# frontend7.net
KiCad netlist of a schematic drawn in EAGLE
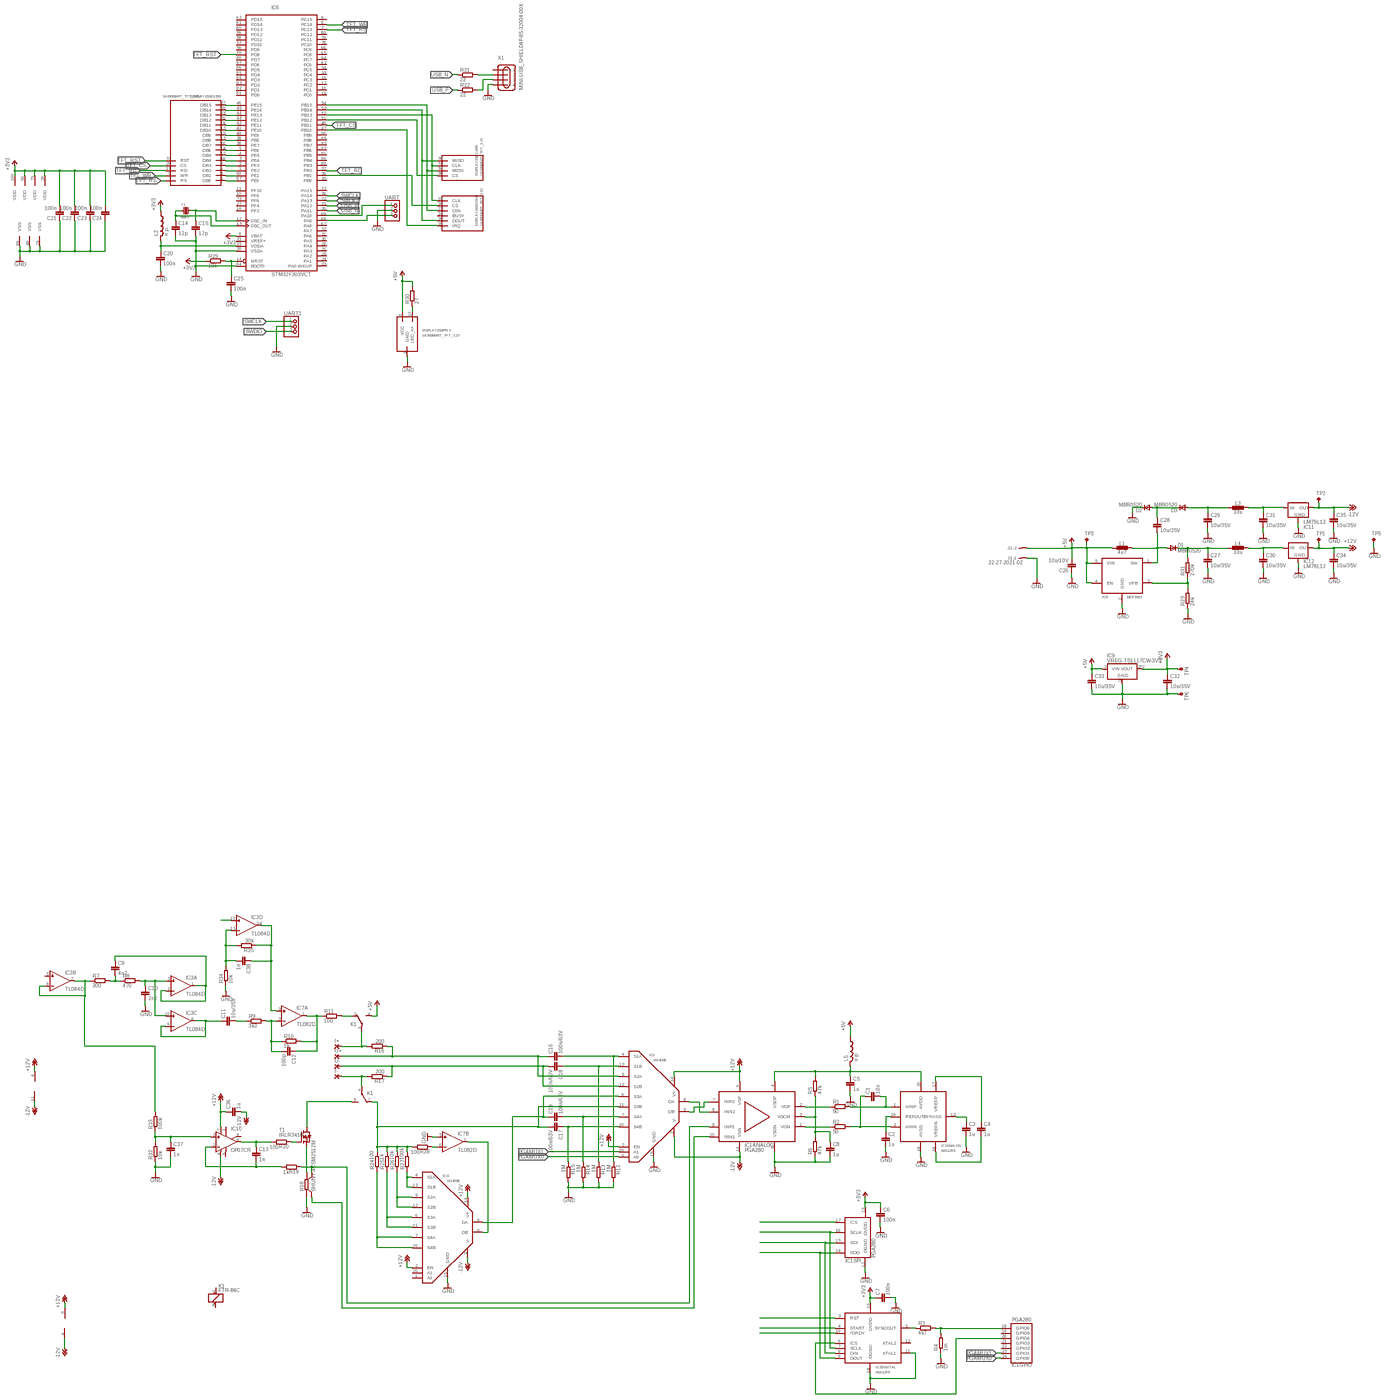
[diagram p0: schematic, sheet 1, overview]
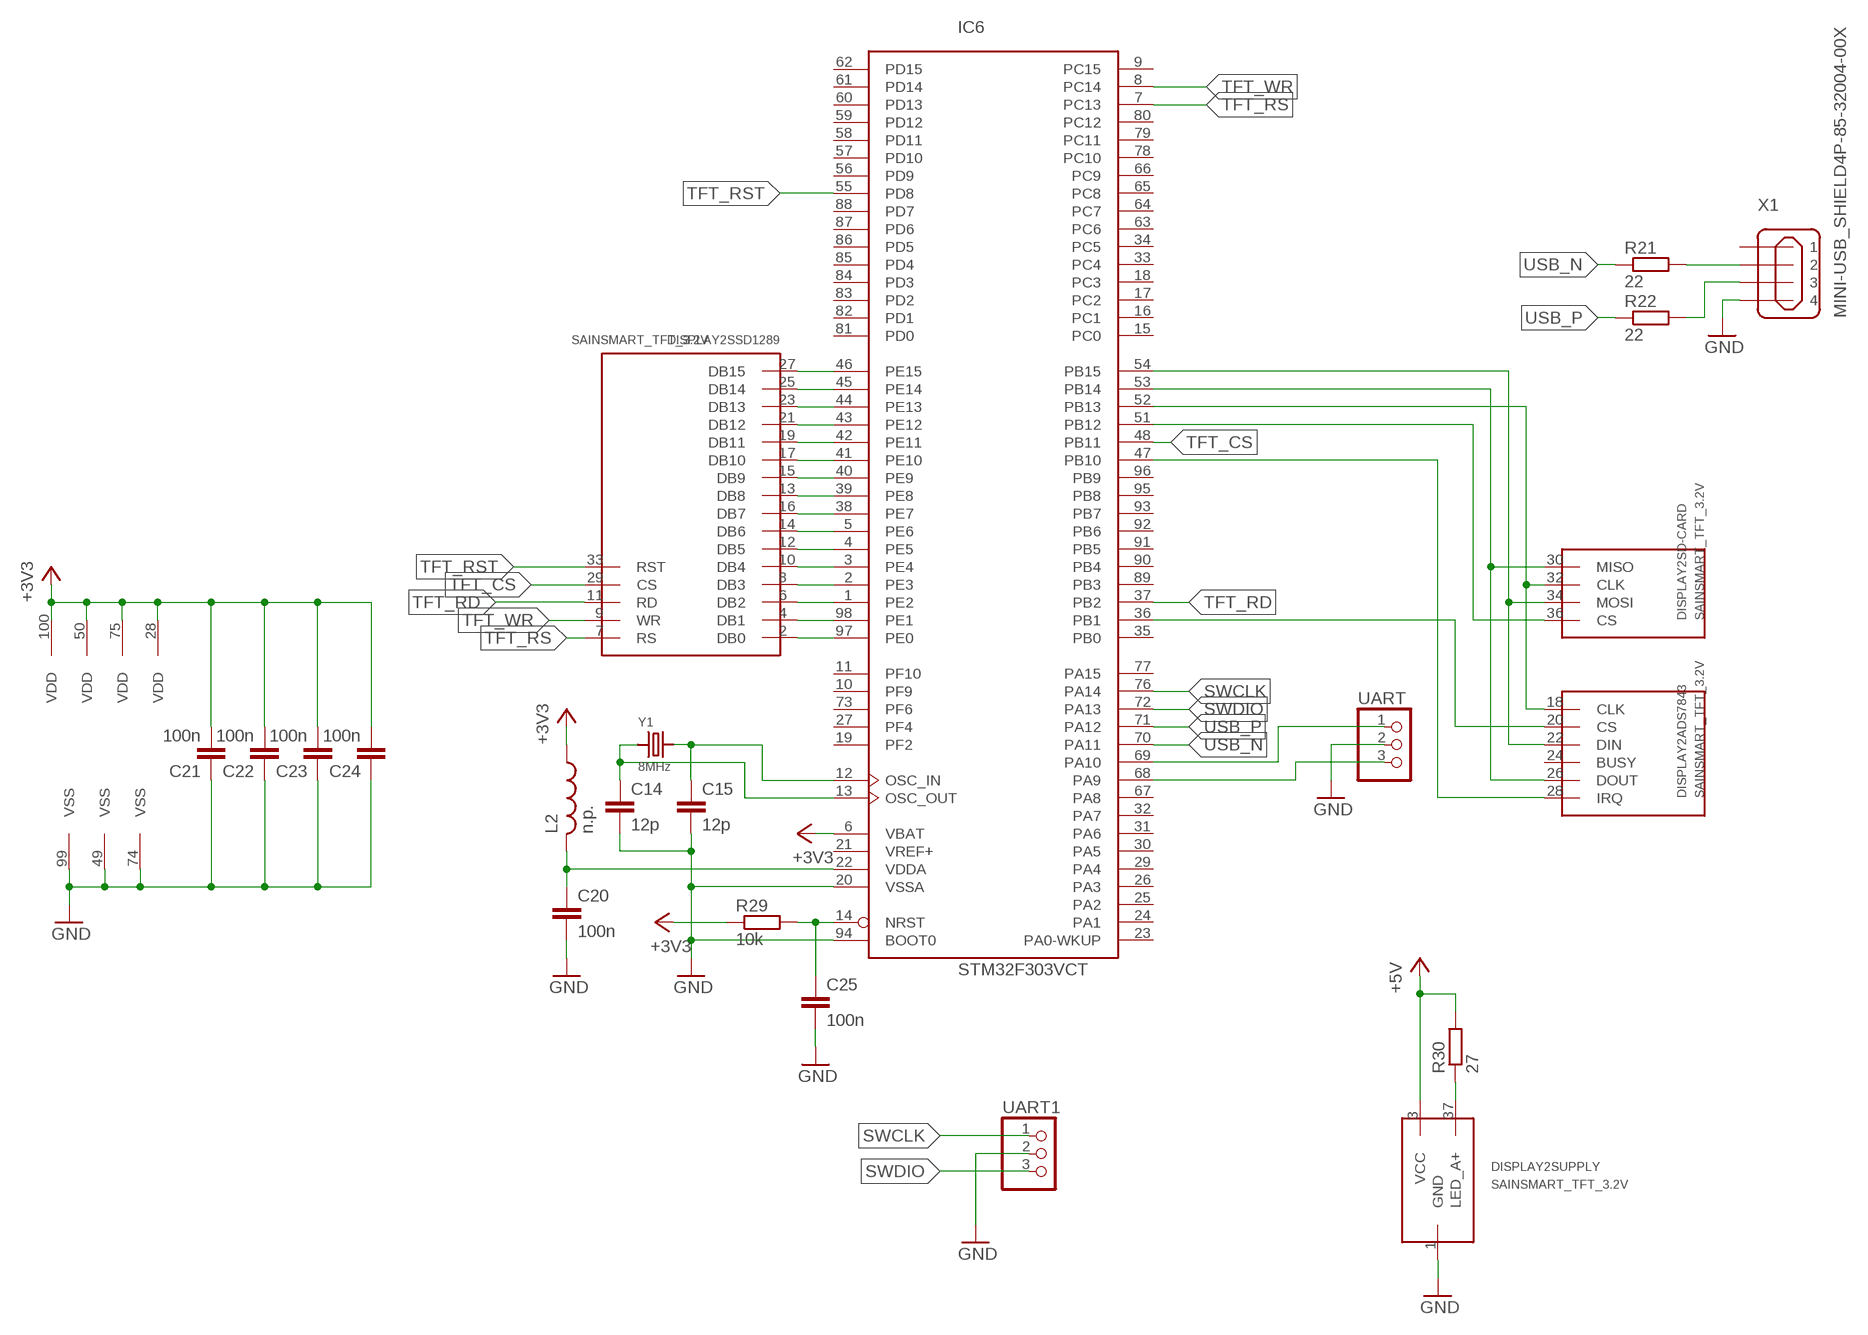
[diagram p1: schematic, sheet 1, part 1 of 4]
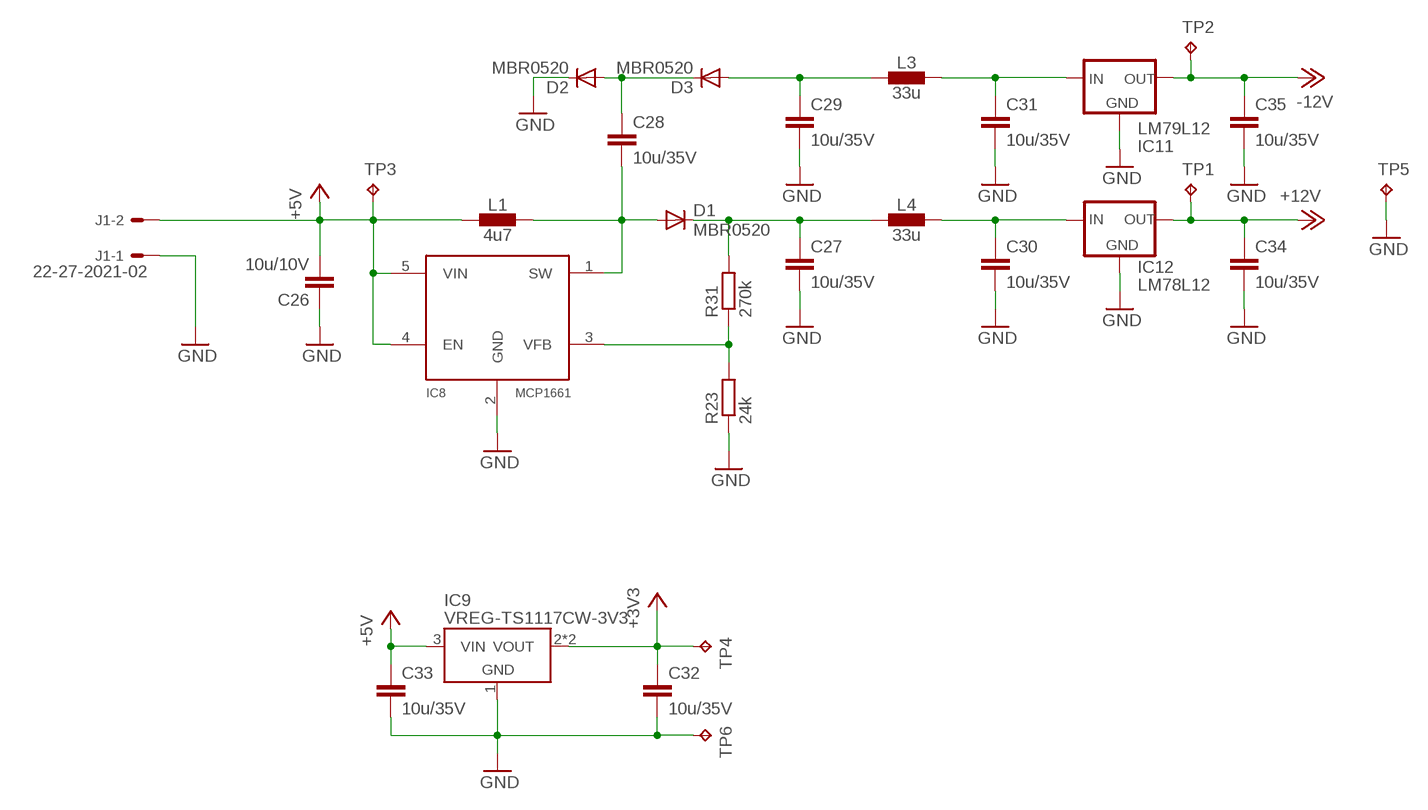
[diagram p2: schematic, sheet 1, part 2 of 4]
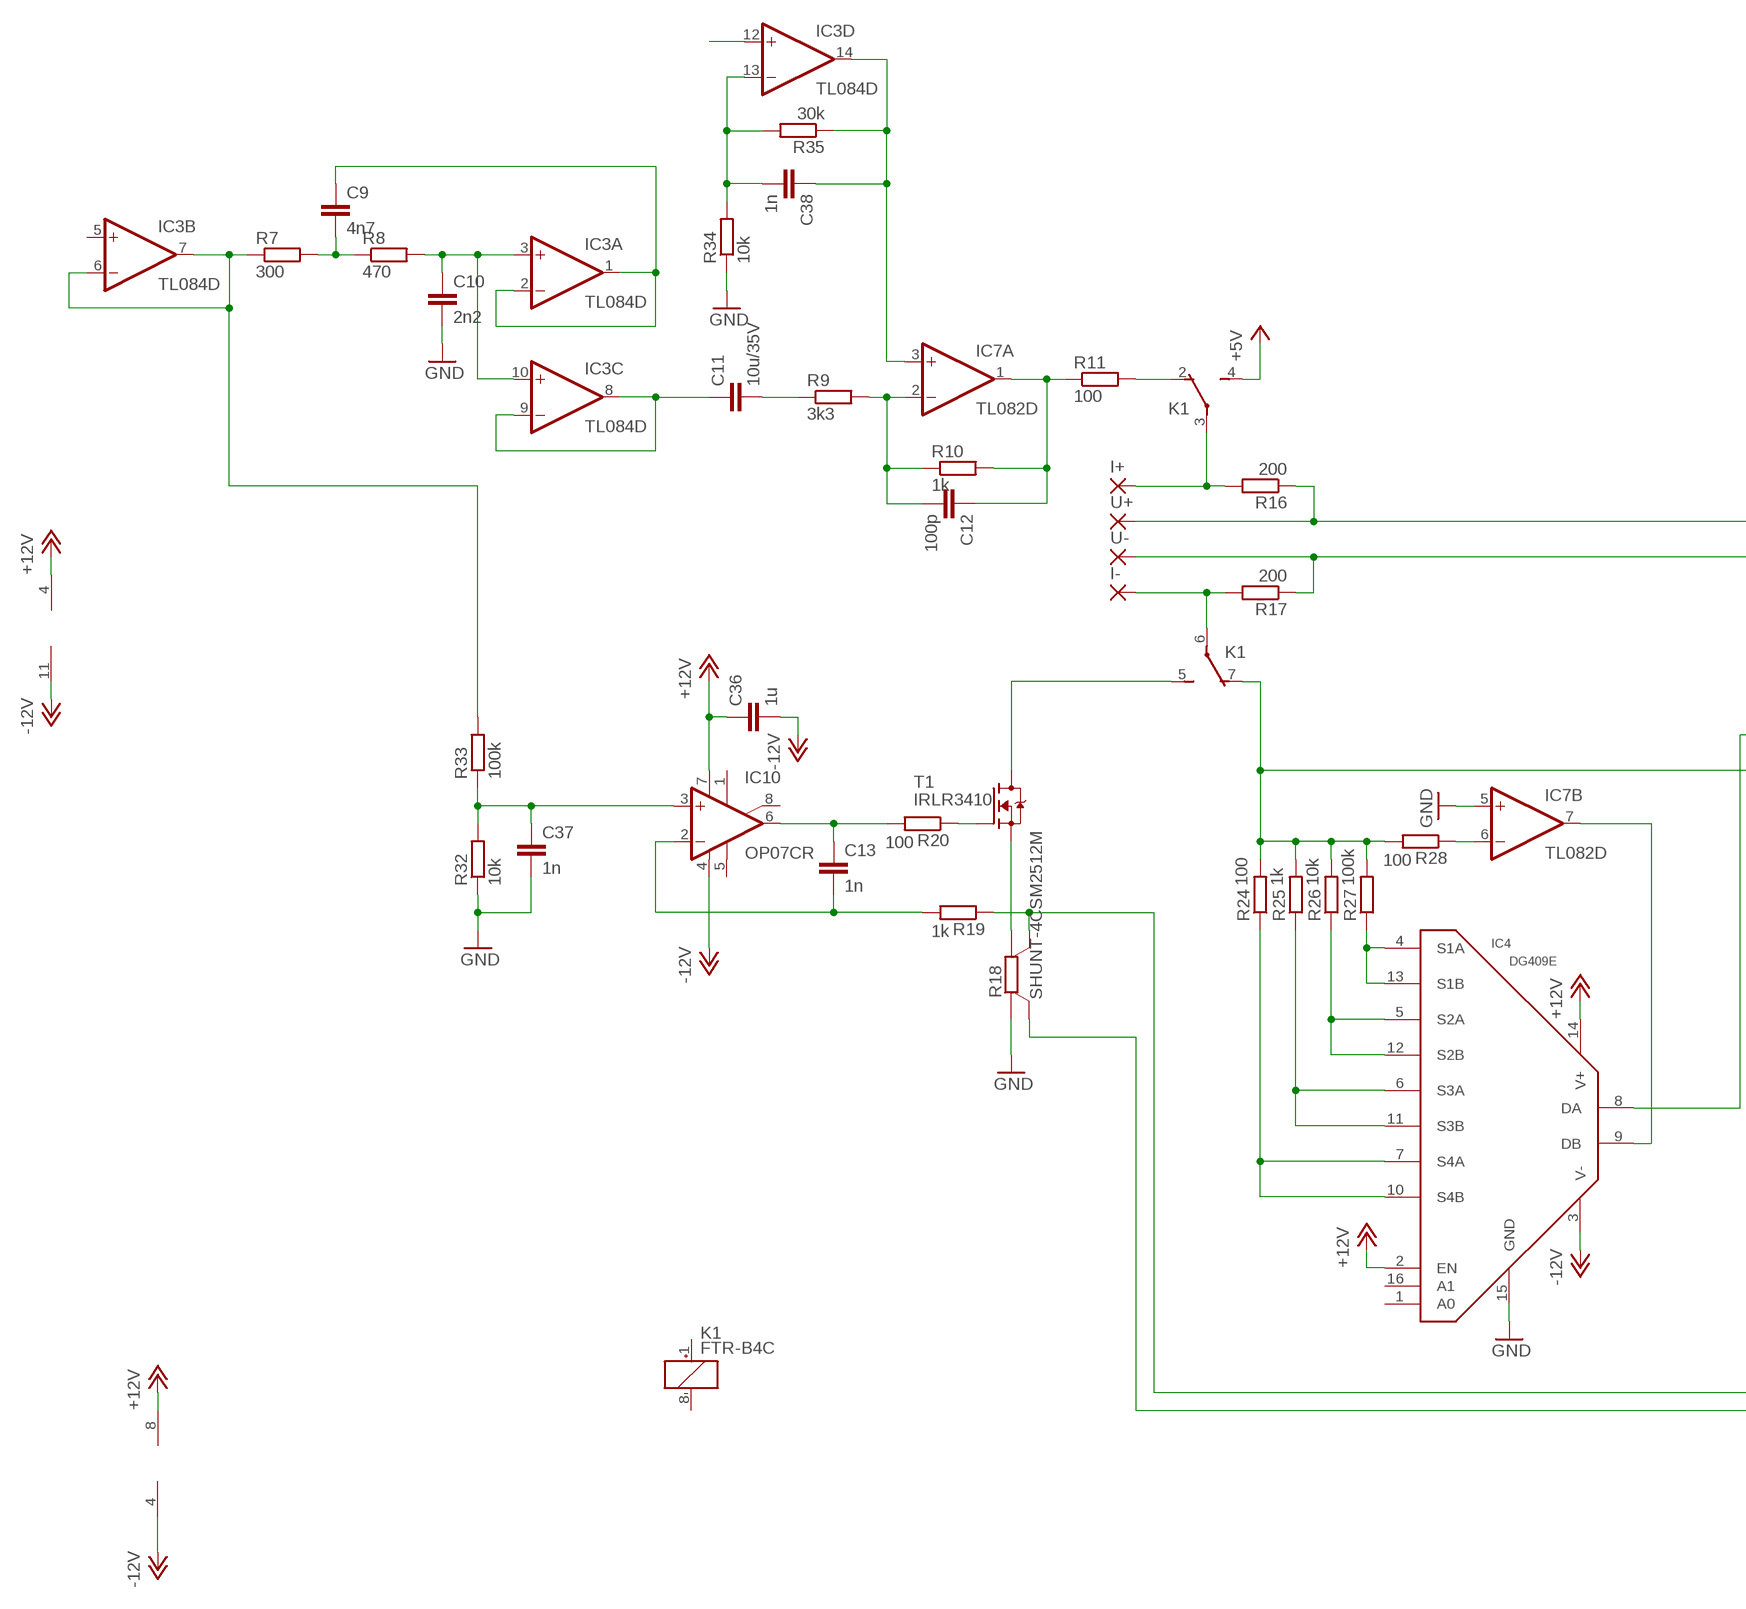
[diagram p3: schematic, sheet 1, part 3 of 4]
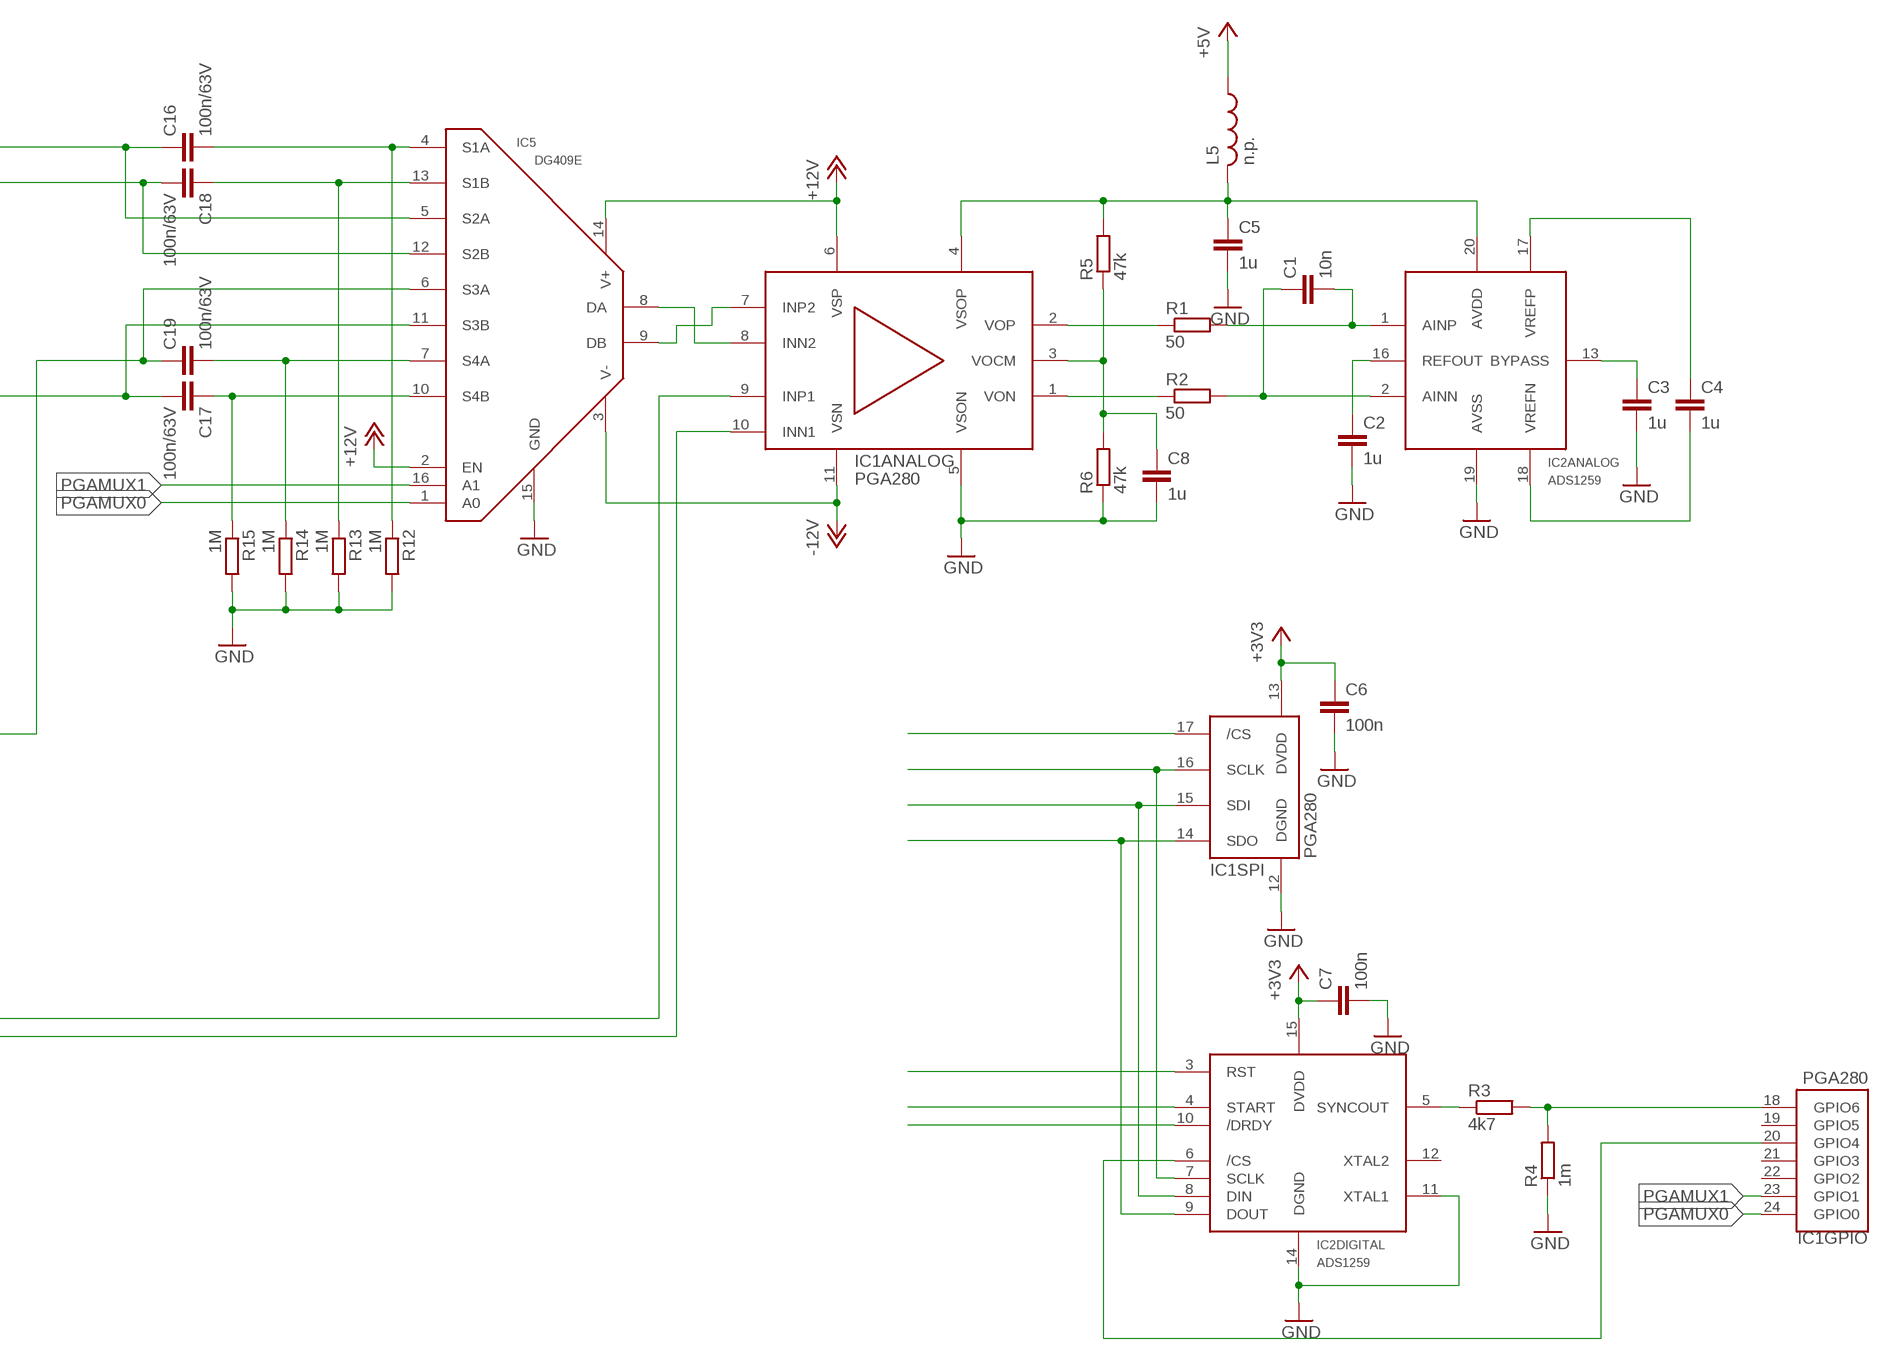
[diagram p4: schematic, sheet 1, part 4 of 4]

(export (version "E")
  (design (tool "Eeschema 10.0.6"))
  (components
    (comp (ref "C1")
      (value "10n")
      (footprint "eagle-import:C0603K")
      (libsource (lib "eagle-import") (part "C-EUC0603K"))
    )
    (comp (ref "C2")
      (value "1u")
      (footprint "eagle-import:C0603K")
      (libsource (lib "eagle-import") (part "C-EUC0603K"))
    )
    (comp (ref "C3")
      (value "1u")
      (footprint "eagle-import:C0603K")
      (libsource (lib "eagle-import") (part "C-EUC0603K"))
    )
    (comp (ref "C4")
      (value "1u")
      (footprint "eagle-import:C0603K")
      (libsource (lib "eagle-import") (part "C-EUC0603K"))
    )
    (comp (ref "C5")
      (value "1u")
      (footprint "eagle-import:C0603K")
      (libsource (lib "eagle-import") (part "C-EUC0603K"))
    )
    (comp (ref "C6")
      (value "100n")
      (footprint "eagle-import:C0603K")
      (libsource (lib "eagle-import") (part "C-EUC0603K"))
    )
    (comp (ref "C7")
      (value "100n")
      (footprint "eagle-import:C0603K")
      (libsource (lib "eagle-import") (part "C-EUC0603K"))
    )
    (comp (ref "C8")
      (value "1u")
      (footprint "eagle-import:C0603K")
      (libsource (lib "eagle-import") (part "C-EUC0603K"))
    )
    (comp (ref "C9")
      (value "4n7")
      (footprint "eagle-import:C0603K")
      (libsource (lib "eagle-import") (part "C-EUC0603K"))
    )
    (comp (ref "C10")
      (value "2n2")
      (footprint "eagle-import:C0603K")
      (libsource (lib "eagle-import") (part "C-EUC0603K"))
    )
    (comp (ref "C11")
      (value "10u/35V")
      (footprint "eagle-import:C1206K")
      (libsource (lib "eagle-import") (part "C-EUC1206K"))
    )
    (comp (ref "C12")
      (value "100p")
      (footprint "eagle-import:C0603K")
      (libsource (lib "eagle-import") (part "C-EUC0603K"))
    )
    (comp (ref "C13")
      (value "1n")
      (footprint "eagle-import:C0603K")
      (libsource (lib "eagle-import") (part "C-EUC0603K"))
    )
    (comp (ref "C14")
      (value "12p")
      (footprint "eagle-import:C0603K")
      (libsource (lib "eagle-import") (part "C-EUC0603K"))
    )
    (comp (ref "C15")
      (value "12p")
      (footprint "eagle-import:C0603K")
      (libsource (lib "eagle-import") (part "C-EUC0603K"))
    )
    (comp (ref "C16")
      (value "100n/63V")
      (footprint "eagle-import:C1206K")
      (libsource (lib "eagle-import") (part "C-EUC1206K"))
    )
    (comp (ref "C17")
      (value "100n/63V")
      (footprint "eagle-import:C1206K")
      (libsource (lib "eagle-import") (part "C-EUC1206K"))
    )
    (comp (ref "C18")
      (value "100n/63V")
      (footprint "eagle-import:C1206K")
      (libsource (lib "eagle-import") (part "C-EUC1206K"))
    )
    (comp (ref "C19")
      (value "100n/63V")
      (footprint "eagle-import:C1206K")
      (libsource (lib "eagle-import") (part "C-EUC1206K"))
    )
    (comp (ref "C20")
      (value "100n")
      (footprint "eagle-import:C0603K")
      (libsource (lib "eagle-import") (part "C-EUC0603K"))
    )
    (comp (ref "C21")
      (value "100n")
      (footprint "eagle-import:C0603K")
      (libsource (lib "eagle-import") (part "C-EUC0603K"))
    )
    (comp (ref "C22")
      (value "100n")
      (footprint "eagle-import:C0603K")
      (libsource (lib "eagle-import") (part "C-EUC0603K"))
    )
    (comp (ref "C23")
      (value "100n")
      (footprint "eagle-import:C0603K")
      (libsource (lib "eagle-import") (part "C-EUC0603K"))
    )
    (comp (ref "C24")
      (value "100n")
      (footprint "eagle-import:C0603K")
      (libsource (lib "eagle-import") (part "C-EUC0603K"))
    )
    (comp (ref "C25")
      (value "100n")
      (footprint "eagle-import:C0603K")
      (libsource (lib "eagle-import") (part "C-EUC0603K"))
    )
    (comp (ref "C26")
      (value "10u/10V")
      (footprint "eagle-import:C1206K")
      (libsource (lib "eagle-import") (part "C-EUC1206K"))
    )
    (comp (ref "C27")
      (value "10u/35V")
      (footprint "eagle-import:C1206K")
      (libsource (lib "eagle-import") (part "C-EUC1206K"))
    )
    (comp (ref "C28")
      (value "10u/35V")
      (footprint "eagle-import:C1206K")
      (libsource (lib "eagle-import") (part "C-EUC1206K"))
    )
    (comp (ref "C29")
      (value "10u/35V")
      (footprint "eagle-import:C1206K")
      (libsource (lib "eagle-import") (part "C-EUC1206K"))
    )
    (comp (ref "C30")
      (value "10u/35V")
      (footprint "eagle-import:C1206K")
      (libsource (lib "eagle-import") (part "C-EUC1206K"))
    )
    (comp (ref "C31")
      (value "10u/35V")
      (footprint "eagle-import:C1206K")
      (libsource (lib "eagle-import") (part "C-EUC1206K"))
    )
    (comp (ref "C32")
      (value "10u/35V")
      (footprint "eagle-import:C1206K")
      (libsource (lib "eagle-import") (part "C-EUC1206K"))
    )
    (comp (ref "C33")
      (value "10u/35V")
      (footprint "eagle-import:C1206K")
      (libsource (lib "eagle-import") (part "C-EUC1206K"))
    )
    (comp (ref "C34")
      (value "10u/35V")
      (footprint "eagle-import:C1206K")
      (libsource (lib "eagle-import") (part "C-EUC1206K"))
    )
    (comp (ref "C35")
      (value "10u/35V")
      (footprint "eagle-import:C1206K")
      (libsource (lib "eagle-import") (part "C-EUC1206K"))
    )
    (comp (ref "C36")
      (value "1u")
      (footprint "eagle-import:C0603K")
      (libsource (lib "eagle-import") (part "C-EUC0603K"))
    )
    (comp (ref "C37")
      (value "1n")
      (footprint "eagle-import:C0603K")
      (libsource (lib "eagle-import") (part "C-EUC0603K"))
    )
    (comp (ref "C38")
      (value "1n")
      (footprint "eagle-import:C0603K")
      (libsource (lib "eagle-import") (part "C-EUC0603K"))
    )
    (comp (ref "D1")
      (value "MBR0520")
      (footprint "eagle-import:SOD123")
      (libsource (lib "eagle-import") (part "DIODE-SOD123"))
    )
    (comp (ref "D2")
      (value "MBR0520")
      (footprint "eagle-import:SOD123")
      (libsource (lib "eagle-import") (part "DIODE-SOD123"))
    )
    (comp (ref "D3")
      (value "MBR0520")
      (footprint "eagle-import:SOD123")
      (libsource (lib "eagle-import") (part "DIODE-SOD123"))
    )
    (comp (ref "DISPLAY2")
      (value "SAINSMART_TFT_3.2V")
      (footprint "eagle-import:SAINSMART_ANGLED")
      (libsource (lib "eagle-import") (part "SAINSMART_TFT_3.2V"))
    )
    (comp (ref "I+")
      (value "SMD5")
      (footprint "eagle-import:SMD2,54-5,08")
      (libsource (lib "eagle-import") (part "SMD5"))
    )
    (comp (ref "I-")
      (value "SMD5")
      (footprint "eagle-import:SMD2,54-5,08")
      (libsource (lib "eagle-import") (part "SMD5"))
    )
    (comp (ref "IC1")
      (value "PGA280")
      (footprint "eagle-import:TSSOP24")
      (libsource (lib "eagle-import") (part "PGA280"))
    )
    (comp (ref "IC2")
      (value "ADS1259")
      (footprint "eagle-import:TSSOP20")
      (libsource (lib "eagle-import") (part "ADS1259"))
    )
    (comp (ref "IC3")
      (value "TL084D")
      (footprint "eagle-import:SO14")
      (libsource (lib "eagle-import") (part "TL084D"))
    )
    (comp (ref "IC4")
      (value "DG409E")
      (footprint "eagle-import:TSSOP16")
      (libsource (lib "eagle-import") (part "DG409E"))
    )
    (comp (ref "IC5")
      (value "DG409E")
      (footprint "eagle-import:TSSOP16")
      (libsource (lib "eagle-import") (part "DG409E"))
    )
    (comp (ref "IC6")
      (value "STM32F303VCT")
      (footprint "eagle-import:LQFP100")
      (libsource (lib "eagle-import") (part "STM32F303VTC"))
    )
    (comp (ref "IC7")
      (value "TL082D")
      (footprint "eagle-import:SO08")
      (libsource (lib "eagle-import") (part "TL082D"))
    )
    (comp (ref "IC8")
      (value "MCP1661")
      (footprint "eagle-import:SOT23-5")
      (libsource (lib "eagle-import") (part "MCP1661"))
    )
    (comp (ref "IC9")
      (value "VREG-TS1117CW-3V3")
      (footprint "eagle-import:SOT223")
      (libsource (lib "eagle-import") (part "VREG-TS1117CW-3V3"))
    )
    (comp (ref "IC10")
      (value "OP07CR")
      (footprint "eagle-import:SO08")
      (libsource (lib "eagle-import") (part "OP07RC"))
    )
    (comp (ref "IC11")
      (value "LM79L12")
      (footprint "eagle-import:SO08")
      (libsource (lib "eagle-import") (part "79LXX-SO_INALL"))
    )
    (comp (ref "IC12")
      (value "LM78L12")
      (footprint "eagle-import:SO08")
      (libsource (lib "eagle-import") (part "78LXX-SO8_GNDALL"))
    )
    (comp (ref "J1")
      (value "22-27-2021-02")
      (footprint "eagle-import:6410-02")
      (libsource (lib "eagle-import") (part "22-?-0227-2021"))
    )
    (comp (ref "K1")
      (value "FTR-B4C")
      (footprint "eagle-import:FTR-B4C")
      (libsource (lib "eagle-import") (part "FTR-B4C"))
    )
    (comp (ref "L1")
      (value "4u7")
      (footprint "eagle-import:L_NR60XX")
      (libsource (lib "eagle-import") (part "INDUCTOR-NR60XX"))
    )
    (comp (ref "L2")
      (value "n.p.")
      (footprint "eagle-import:R0603")
      (libsource (lib "eagle-import") (part "INDUCTOR0603"))
    )
    (comp (ref "L3")
      (value "33u")
      (footprint "eagle-import:L_1212")
      (libsource (lib "eagle-import") (part "INDUCTOR-1212"))
    )
    (comp (ref "L4")
      (value "33u")
      (footprint "eagle-import:L_1212")
      (libsource (lib "eagle-import") (part "INDUCTOR-1212"))
    )
    (comp (ref "L5")
      (value "n.p.")
      (footprint "eagle-import:R0603")
      (libsource (lib "eagle-import") (part "INDUCTOR0603"))
    )
    (comp (ref "R1")
      (value "50")
      (footprint "eagle-import:R0603")
      (libsource (lib "eagle-import") (part "resistor_R-EU_R0603"))
    )
    (comp (ref "R2")
      (value "50")
      (footprint "eagle-import:R0603")
      (libsource (lib "eagle-import") (part "resistor_R-EU_R0603"))
    )
    (comp (ref "R3")
      (value "4k7")
      (footprint "eagle-import:R0603")
      (libsource (lib "eagle-import") (part "resistor_R-EU_R0603"))
    )
    (comp (ref "R4")
      (value "1m")
      (footprint "eagle-import:R0603")
      (libsource (lib "eagle-import") (part "resistor_R-EU_R0603"))
    )
    (comp (ref "R5")
      (value "47k")
      (footprint "eagle-import:R0603")
      (libsource (lib "eagle-import") (part "resistor_R-EU_R0603"))
    )
    (comp (ref "R6")
      (value "47k")
      (footprint "eagle-import:R0603")
      (libsource (lib "eagle-import") (part "resistor_R-EU_R0603"))
    )
    (comp (ref "R7")
      (value "300")
      (footprint "eagle-import:R0603")
      (libsource (lib "eagle-import") (part "R-EU_R0603"))
    )
    (comp (ref "R8")
      (value "470")
      (footprint "eagle-import:R0603")
      (libsource (lib "eagle-import") (part "R-EU_R0603"))
    )
    (comp (ref "R9")
      (value "3k3")
      (footprint "eagle-import:R0603")
      (libsource (lib "eagle-import") (part "R-EU_R0603"))
    )
    (comp (ref "R10")
      (value "1k")
      (footprint "eagle-import:R0603")
      (libsource (lib "eagle-import") (part "R-EU_R0603"))
    )
    (comp (ref "R11")
      (value "100")
      (footprint "eagle-import:R0603")
      (libsource (lib "eagle-import") (part "R-EU_R0603"))
    )
    (comp (ref "R12")
      (value "1M")
      (footprint "eagle-import:R0603")
      (libsource (lib "eagle-import") (part "R-EU_R0603"))
    )
    (comp (ref "R13")
      (value "1M")
      (footprint "eagle-import:R0603")
      (libsource (lib "eagle-import") (part "R-EU_R0603"))
    )
    (comp (ref "R14")
      (value "1M")
      (footprint "eagle-import:R0603")
      (libsource (lib "eagle-import") (part "R-EU_R0603"))
    )
    (comp (ref "R15")
      (value "1M")
      (footprint "eagle-import:R0603")
      (libsource (lib "eagle-import") (part "R-EU_R0603"))
    )
    (comp (ref "R16")
      (value "200")
      (footprint "eagle-import:R0603")
      (libsource (lib "eagle-import") (part "resistor_R-EU_R0603"))
    )
    (comp (ref "R17")
      (value "200")
      (footprint "eagle-import:R0603")
      (libsource (lib "eagle-import") (part "resistor_R-EU_R0603"))
    )
    (comp (ref "R18")
      (value "SHUNT-4CSM2512M")
      (footprint "eagle-import:CSM2512M")
      (libsource (lib "eagle-import") (part "SHUNT-4CSM2512M"))
    )
    (comp (ref "R19")
      (value "1k")
      (footprint "eagle-import:R0603")
      (libsource (lib "eagle-import") (part "R-EU_R0603"))
    )
    (comp (ref "R20")
      (value "100")
      (footprint "eagle-import:R0603")
      (libsource (lib "eagle-import") (part "R-EU_R0603"))
    )
    (comp (ref "R21")
      (value "22")
      (footprint "eagle-import:R0603")
      (libsource (lib "eagle-import") (part "resistor_R-EU_R0603"))
    )
    (comp (ref "R22")
      (value "22")
      (footprint "eagle-import:R0603")
      (libsource (lib "eagle-import") (part "resistor_R-EU_R0603"))
    )
    (comp (ref "R23")
      (value "24k")
      (footprint "eagle-import:R0603")
      (libsource (lib "eagle-import") (part "R-EU_R0603"))
    )
    (comp (ref "R24")
      (value "100")
      (footprint "eagle-import:R0603")
      (libsource (lib "eagle-import") (part "R-EU_R0603"))
    )
    (comp (ref "R25")
      (value "1k")
      (footprint "eagle-import:R0603")
      (libsource (lib "eagle-import") (part "R-EU_R0603"))
    )
    (comp (ref "R26")
      (value "10k")
      (footprint "eagle-import:R0603")
      (libsource (lib "eagle-import") (part "R-EU_R0603"))
    )
    (comp (ref "R27")
      (value "100k")
      (footprint "eagle-import:R0603")
      (libsource (lib "eagle-import") (part "R-EU_R0603"))
    )
    (comp (ref "R28")
      (value "100")
      (footprint "eagle-import:R0603")
      (libsource (lib "eagle-import") (part "R-EU_R0603"))
    )
    (comp (ref "R29")
      (value "10k")
      (footprint "eagle-import:R0603")
      (libsource (lib "eagle-import") (part "resistor_R-EU_R0603"))
    )
    (comp (ref "R30")
      (value "27")
      (footprint "eagle-import:R1206")
      (libsource (lib "eagle-import") (part "resistor_R-EU_R1206"))
    )
    (comp (ref "R31")
      (value "270k")
      (footprint "eagle-import:R0603")
      (libsource (lib "eagle-import") (part "R-EU_R0603"))
    )
    (comp (ref "R32")
      (value "10k")
      (footprint "eagle-import:R0603")
      (libsource (lib "eagle-import") (part "R-EU_R0603"))
    )
    (comp (ref "R33")
      (value "100k")
      (footprint "eagle-import:R0603")
      (libsource (lib "eagle-import") (part "R-EU_R0603"))
    )
    (comp (ref "R34")
      (value "10k")
      (footprint "eagle-import:R0603")
      (libsource (lib "eagle-import") (part "R-EU_R0603"))
    )
    (comp (ref "R35")
      (value "30k")
      (footprint "eagle-import:R0603")
      (libsource (lib "eagle-import") (part "R-EU_R0603"))
    )
    (comp (ref "T1")
      (value "IRLR3410")
      (footprint "eagle-import:TO252")
      (libsource (lib "eagle-import") (part "IRLR3410"))
    )
    (comp (ref "TP1")
      (value "TPB2,54")
      (footprint "eagle-import:B2,54")
      (libsource (lib "eagle-import") (part "TPB2,54"))
    )
    (comp (ref "TP2")
      (value "TPB2,54")
      (footprint "eagle-import:B2,54")
      (libsource (lib "eagle-import") (part "TPB2,54"))
    )
    (comp (ref "TP3")
      (value "TPB2,54")
      (footprint "eagle-import:B2,54")
      (libsource (lib "eagle-import") (part "TPB2,54"))
    )
    (comp (ref "TP4")
      (value "TPB2,54")
      (footprint "eagle-import:B2,54")
      (libsource (lib "eagle-import") (part "TPB2,54"))
    )
    (comp (ref "TP5")
      (value "TPB2,54")
      (footprint "eagle-import:B2,54")
      (libsource (lib "eagle-import") (part "TPB2,54"))
    )
    (comp (ref "TP6")
      (value "TPB2,54")
      (footprint "eagle-import:B2,54")
      (libsource (lib "eagle-import") (part "TPB2,54"))
    )
    (comp (ref "U+")
      (value "SMD5")
      (footprint "eagle-import:SMD2,54-5,08")
      (libsource (lib "eagle-import") (part "SMD5"))
    )
    (comp (ref "U-")
      (value "SMD5")
      (footprint "eagle-import:SMD2,54-5,08")
      (libsource (lib "eagle-import") (part "SMD5"))
    )
    (comp (ref "UART")
      (value "PINHD-1X3")
      (footprint "eagle-import:1X03")
      (libsource (lib "eagle-import") (part "PINHD-1X3"))
    )
    (comp (ref "UART1")
      (value "PINHD-1X3")
      (footprint "eagle-import:1X03")
      (libsource (lib "eagle-import") (part "PINHD-1X3"))
    )
    (comp (ref "X1")
      (value "MINI-USB_SHIELD4P-85-32004-00X")
      (footprint "eagle-import:85-32004-00X")
      (libsource (lib "eagle-import") (part "MINI-USB_SHIELD4P-85-32004-00X"))
    )
    (comp (ref "Y1")
      (value "8MHz")
      (footprint "eagle-import:3.2X2.5MM")
      (libsource (lib "eagle-import") (part "CRYSTAL.3.2X2.5MM"))
    )
  )
  (nets
    (net (code "1") (name "+3V3") (class "Default")
      (node (ref "C21") (pin "2") (pinfunction "2_2") (pintype "passive"))
      (node (ref "C22") (pin "2") (pinfunction "2_2") (pintype "passive"))
      (node (ref "C23") (pin "2") (pinfunction "2_2") (pintype "passive"))
      (node (ref "C24") (pin "2") (pinfunction "2_2") (pintype "passive"))
      (node (ref "C32") (pin "1") (pinfunction "1_1") (pintype "passive"))
      (node (ref "C6") (pin "1") (pinfunction "1_1") (pintype "passive"))
      (node (ref "C7") (pin "1") (pinfunction "1_1") (pintype "passive"))
      (node (ref "IC1") (pin "13") (pinfunction "DVDD_13") (pintype "bidirectional"))
      (node (ref "IC2") (pin "15") (pinfunction "DVDD_15") (pintype "bidirectional"))
      (node (ref "IC6") (pin "100") (pinfunction "VDD_100") (pintype "power_in"))
      (node (ref "IC6") (pin "28") (pinfunction "VDD_28") (pintype "power_in"))
      (node (ref "IC6") (pin "50") (pinfunction "VDD_50") (pintype "power_in"))
      (node (ref "IC6") (pin "6") (pinfunction "VBAT_6") (pintype "power_in"))
      (node (ref "IC6") (pin "75") (pinfunction "VDD_75") (pintype "power_in"))
      (node (ref "IC9") (pin "2") (pinfunction "VOUT_2") (pintype "power_in"))
      (node (ref "IC9") (pin "4") (pinfunction "VOUT_4") (pintype "power_in"))
      (node (ref "L2") (pin "1") (pinfunction "1_1") (pintype "passive"))
      (node (ref "R29") (pin "1") (pinfunction "1_1") (pintype "passive"))
      (node (ref "TP4") (pin "TP") (pinfunction "TP_TP") (pintype "input"))
    )
    (net (code "2") (name "+5V") (class "Default")
      (node (ref "C26") (pin "2") (pinfunction "2_2") (pintype "passive"))
      (node (ref "C33") (pin "1") (pinfunction "1_1") (pintype "passive"))
      (node (ref "DISPLAY2") (pin "3") (pinfunction "VCC_3") (pintype "bidirectional"))
      (node (ref "IC8") (pin "4") (pinfunction "EN_4") (pintype "bidirectional"))
      (node (ref "IC8") (pin "5") (pinfunction "VIN_5") (pintype "bidirectional"))
      (node (ref "IC9") (pin "3") (pinfunction "VIN_3") (pintype "power_in"))
      (node (ref "J1") (pin "2") (pinfunction "S_2") (pintype "passive"))
      (node (ref "K1") (pin "4") (pinfunction "S_4") (pintype "passive"))
      (node (ref "L1") (pin "1") (pinfunction "1_1") (pintype "passive"))
      (node (ref "L5") (pin "1") (pinfunction "1_1") (pintype "passive"))
      (node (ref "R30") (pin "2") (pinfunction "2_2") (pintype "passive"))
      (node (ref "TP3") (pin "TP") (pinfunction "TP_TP") (pintype "input"))
    )
    (net (code "3") (name "+12V") (class "Default")
      (node (ref "C34") (pin "1") (pinfunction "1_1") (pintype "passive"))
      (node (ref "C36") (pin "1") (pinfunction "1_1") (pintype "passive"))
      (node (ref "IC1") (pin "6") (pinfunction "VSP_6") (pintype "bidirectional"))
      (node (ref "IC10") (pin "7") (pinfunction "V+_7") (pintype "power_in"))
      (node (ref "IC12") (pin "1") (pinfunction "OUT_1") (pintype "passive"))
      (node (ref "IC3") (pin "4") (pinfunction "V+_4") (pintype "power_in"))
      (node (ref "IC4") (pin "14") (pinfunction "V+_14") (pintype "bidirectional"))
      (node (ref "IC4") (pin "2") (pinfunction "EN_2") (pintype "bidirectional"))
      (node (ref "IC5") (pin "14") (pinfunction "V+_14") (pintype "bidirectional"))
      (node (ref "IC5") (pin "2") (pinfunction "EN_2") (pintype "bidirectional"))
      (node (ref "IC7") (pin "8") (pinfunction "V+_8") (pintype "power_in"))
      (node (ref "TP1") (pin "TP") (pinfunction "TP_TP") (pintype "input"))
    )
    (net (code "4") (name "-12V") (class "Default")
      (node (ref "C35") (pin "1") (pinfunction "1_1") (pintype "passive"))
      (node (ref "C36") (pin "2") (pinfunction "2_2") (pintype "passive"))
      (node (ref "IC1") (pin "11") (pinfunction "VSN_11") (pintype "bidirectional"))
      (node (ref "IC10") (pin "4") (pinfunction "V-_4") (pintype "power_in"))
      (node (ref "IC11") (pin "1") (pinfunction "OUT_1") (pintype "passive"))
      (node (ref "IC3") (pin "11") (pinfunction "V-_11") (pintype "power_in"))
      (node (ref "IC4") (pin "3") (pinfunction "V-_3") (pintype "bidirectional"))
      (node (ref "IC5") (pin "3") (pinfunction "V-_3") (pintype "bidirectional"))
      (node (ref "IC7") (pin "4") (pinfunction "V-_4") (pintype "power_in"))
      (node (ref "TP2") (pin "TP") (pinfunction "TP_TP") (pintype "input"))
    )
    (net (code "5") (name "/VREF+") (class "Default")
      (node (ref "IC6") (pin "21") (pinfunction "VREF+_21") (pintype "power_in"))
    )
    (net (code "6") (name "GND") (class "Default")
      (node (ref "C10") (pin "2") (pinfunction "2_2") (pintype "passive"))
      (node (ref "C14") (pin "2") (pinfunction "2_2") (pintype "passive"))
      (node (ref "C15") (pin "2") (pinfunction "2_2") (pintype "passive"))
      (node (ref "C2") (pin "2") (pinfunction "2_2") (pintype "passive"))
      (node (ref "C20") (pin "2") (pinfunction "2_2") (pintype "passive"))
      (node (ref "C21") (pin "1") (pinfunction "1_1") (pintype "passive"))
      (node (ref "C22") (pin "1") (pinfunction "1_1") (pintype "passive"))
      (node (ref "C23") (pin "1") (pinfunction "1_1") (pintype "passive"))
      (node (ref "C24") (pin "1") (pinfunction "1_1") (pintype "passive"))
      (node (ref "C25") (pin "2") (pinfunction "2_2") (pintype "passive"))
      (node (ref "C26") (pin "1") (pinfunction "1_1") (pintype "passive"))
      (node (ref "C27") (pin "2") (pinfunction "2_2") (pintype "passive"))
      (node (ref "C29") (pin "2") (pinfunction "2_2") (pintype "passive"))
      (node (ref "C3") (pin "2") (pinfunction "2_2") (pintype "passive"))
      (node (ref "C30") (pin "2") (pinfunction "2_2") (pintype "passive"))
      (node (ref "C31") (pin "2") (pinfunction "2_2") (pintype "passive"))
      (node (ref "C32") (pin "2") (pinfunction "2_2") (pintype "passive"))
      (node (ref "C33") (pin "2") (pinfunction "2_2") (pintype "passive"))
      (node (ref "C34") (pin "2") (pinfunction "2_2") (pintype "passive"))
      (node (ref "C35") (pin "2") (pinfunction "2_2") (pintype "passive"))
      (node (ref "C37") (pin "2") (pinfunction "2_2") (pintype "passive"))
      (node (ref "C5") (pin "2") (pinfunction "2_2") (pintype "passive"))
      (node (ref "C6") (pin "2") (pinfunction "2_2") (pintype "passive"))
      (node (ref "C7") (pin "2") (pinfunction "2_2") (pintype "passive"))
      (node (ref "C8") (pin "2") (pinfunction "2_2") (pintype "passive"))
      (node (ref "D2") (pin "C") (pinfunction "C_C") (pintype "passive"))
      (node (ref "DISPLAY2") (pin "1") (pinfunction "GND_1") (pintype "bidirectional"))
      (node (ref "IC1") (pin "12") (pinfunction "DGND_12") (pintype "bidirectional"))
      (node (ref "IC1") (pin "5") (pinfunction "VSON_5") (pintype "bidirectional"))
      (node (ref "IC11") (pin "5") (pinfunction "GND_5") (pintype "input"))
      (node (ref "IC12") (pin "2") (pinfunction "GND_2") (pintype "input"))
      (node (ref "IC12") (pin "3") (pinfunction "GND_3") (pintype "input"))
      (node (ref "IC12") (pin "6") (pinfunction "GND_6") (pintype "input"))
      (node (ref "IC12") (pin "7") (pinfunction "GND_7") (pintype "input"))
      (node (ref "IC2") (pin "11") (pinfunction "XTAL1_11") (pintype "bidirectional"))
      (node (ref "IC2") (pin "14") (pinfunction "DGND_14") (pintype "bidirectional"))
      (node (ref "IC2") (pin "19") (pinfunction "AVSS_19") (pintype "bidirectional"))
      (node (ref "IC4") (pin "15") (pinfunction "GND_15") (pintype "bidirectional"))
      (node (ref "IC5") (pin "15") (pinfunction "GND_15") (pintype "bidirectional"))
      (node (ref "IC6") (pin "20") (pinfunction "VSSA_20") (pintype "power_in"))
      (node (ref "IC6") (pin "49") (pinfunction "VSS_49") (pintype "power_in"))
      (node (ref "IC6") (pin "74") (pinfunction "VSS_74") (pintype "power_in"))
      (node (ref "IC6") (pin "94") (pinfunction "BOOT0_94") (pintype "input"))
      (node (ref "IC6") (pin "99") (pinfunction "VSS_99") (pintype "power_in"))
      (node (ref "IC7") (pin "5") (pinfunction "+IN_5") (pintype "input"))
      (node (ref "IC8") (pin "2") (pinfunction "GND_2") (pintype "bidirectional"))
      (node (ref "IC9") (pin "1") (pinfunction "GND_1") (pintype "power_in"))
      (node (ref "J1") (pin "1") (pinfunction "S_1") (pintype "passive"))
      (node (ref "R12") (pin "2") (pinfunction "2_2") (pintype "passive"))
      (node (ref "R13") (pin "2") (pinfunction "2_2") (pintype "passive"))
      (node (ref "R14") (pin "2") (pinfunction "2_2") (pintype "passive"))
      (node (ref "R15") (pin "2") (pinfunction "2_2") (pintype "passive"))
      (node (ref "R18") (pin "I2") (pinfunction "I2_I2") (pintype "passive"))
      (node (ref "R23") (pin "1") (pinfunction "1_1") (pintype "passive"))
      (node (ref "R32") (pin "1") (pinfunction "1_1") (pintype "passive"))
      (node (ref "R34") (pin "1") (pinfunction "1_1") (pintype "passive"))
      (node (ref "R4") (pin "1") (pinfunction "1_1") (pintype "passive"))
      (node (ref "R6") (pin "1") (pinfunction "1_1") (pintype "passive"))
      (node (ref "TP5") (pin "TP") (pinfunction "TP_TP") (pintype "input"))
      (node (ref "TP6") (pin "TP") (pinfunction "TP_TP") (pintype "input"))
      (node (ref "UART") (pin "2") (pinfunction "2_2") (pintype "passive"))
      (node (ref "UART1") (pin "2") (pinfunction "2_2") (pintype "passive"))
      (node (ref "X1") (pin "4") (pinfunction "4_4") (pintype "passive"))
    )
    (net (code "7") (name "Net-(C9-Pad2)") (class "Default")
      (node (ref "C9") (pin "2") (pinfunction "2_2") (pintype "passive"))
      (node (ref "R7") (pin "2") (pinfunction "2_2") (pintype "passive"))
      (node (ref "R8") (pin "1") (pinfunction "1_1") (pintype "passive"))
    )
    (net (code "8") (name "Net-(C11-Pad2)") (class "Default")
      (node (ref "C11") (pin "2") (pinfunction "2_2") (pintype "passive"))
      (node (ref "R9") (pin "1") (pinfunction "1_1") (pintype "passive"))
    )
    (net (code "9") (name "Net-(C27-Pad1)") (class "Default")
      (node (ref "C27") (pin "1") (pinfunction "1_1") (pintype "passive"))
      (node (ref "D1") (pin "C") (pinfunction "C_C") (pintype "passive"))
      (node (ref "L4") (pin "1") (pinfunction "1_1") (pintype "passive"))
      (node (ref "R31") (pin "2") (pinfunction "2_2") (pintype "passive"))
    )
    (net (code "10") (name "Net-(C28-Pad1)") (class "Default")
      (node (ref "C28") (pin "1") (pinfunction "1_1") (pintype "passive"))
      (node (ref "D2") (pin "A") (pinfunction "A_A") (pintype "passive"))
      (node (ref "D3") (pin "C") (pinfunction "C_C") (pintype "passive"))
    )
    (net (code "11") (name "Net-(C29-Pad1)") (class "Default")
      (node (ref "C29") (pin "1") (pinfunction "1_1") (pintype "passive"))
      (node (ref "D3") (pin "A") (pinfunction "A_A") (pintype "passive"))
      (node (ref "L3") (pin "1") (pinfunction "1_1") (pintype "passive"))
    )
    (net (code "12") (name "Net-(C31-Pad1)") (class "Default")
      (node (ref "C31") (pin "1") (pinfunction "1_1") (pintype "passive"))
      (node (ref "IC11") (pin "2") (pinfunction "IN_2") (pintype "input"))
      (node (ref "IC11") (pin "3") (pinfunction "IN_3") (pintype "input"))
      (node (ref "IC11") (pin "6") (pinfunction "IN_6") (pintype "input"))
      (node (ref "IC11") (pin "7") (pinfunction "IN_7") (pintype "input"))
      (node (ref "L3") (pin "2") (pinfunction "2_2") (pintype "passive"))
    )
    (net (code "13") (name "Net-(DISPLAY2A-CLK)") (class "Default")
      (node (ref "DISPLAY2") (pin "18") (pinfunction "CLK_18") (pintype "bidirectional"))
      (node (ref "DISPLAY2") (pin "32") (pinfunction "CLK_32") (pintype "bidirectional"))
      (node (ref "IC6") (pin "52") (pinfunction "PB13_52") (pintype "bidirectional"))
    )
    (net (code "14") (name "Net-(DISPLAY2A-CS)") (class "Default")
      (node (ref "DISPLAY2") (pin "20") (pinfunction "CS_20") (pintype "bidirectional"))
      (node (ref "IC6") (pin "36") (pinfunction "PB1_36") (pintype "bidirectional"))
    )
    (net (code "15") (name "Net-(DISPLAY2A-DIN)") (class "Default")
      (node (ref "DISPLAY2") (pin "22") (pinfunction "DIN_22") (pintype "bidirectional"))
      (node (ref "DISPLAY2") (pin "34") (pinfunction "MOSI_34") (pintype "bidirectional"))
      (node (ref "IC6") (pin "54") (pinfunction "PB15_54") (pintype "bidirectional"))
    )
    (net (code "16") (name "Net-(DISPLAY2A-DOUT)") (class "Default")
      (node (ref "DISPLAY2") (pin "26") (pinfunction "DOUT_26") (pintype "bidirectional"))
      (node (ref "DISPLAY2") (pin "30") (pinfunction "MISO_30") (pintype "bidirectional"))
      (node (ref "IC6") (pin "53") (pinfunction "PB14_53") (pintype "bidirectional"))
    )
    (net (code "17") (name "Net-(DISPLAY2A-IRQ)") (class "Default")
      (node (ref "DISPLAY2") (pin "28") (pinfunction "IRQ_28") (pintype "bidirectional"))
      (node (ref "IC6") (pin "47") (pinfunction "PB10_47") (pintype "bidirectional"))
    )
    (net (code "18") (name "Net-(DISPLAY2B-CS)") (class "Default")
      (node (ref "DISPLAY2") (pin "36") (pinfunction "CS_36") (pintype "bidirectional"))
      (node (ref "IC6") (pin "51") (pinfunction "PB12_51") (pintype "bidirectional"))
    )
    (net (code "19") (name "Net-(DISPLAY2C-DB0)") (class "Default")
      (node (ref "DISPLAY2") (pin "2") (pinfunction "DB0_2") (pintype "bidirectional"))
      (node (ref "IC6") (pin "97") (pinfunction "PE0_97") (pintype "bidirectional"))
    )
    (net (code "20") (name "Net-(DISPLAY2C-DB1)") (class "Default")
      (node (ref "DISPLAY2") (pin "4") (pinfunction "DB1_4") (pintype "bidirectional"))
      (node (ref "IC6") (pin "98") (pinfunction "PE1_98") (pintype "bidirectional"))
    )
    (net (code "21") (name "Net-(DISPLAY2C-DB2)") (class "Default")
      (node (ref "DISPLAY2") (pin "6") (pinfunction "DB2_6") (pintype "bidirectional"))
      (node (ref "IC6") (pin "1") (pinfunction "PE2_1") (pintype "bidirectional"))
    )
    (net (code "22") (name "Net-(DISPLAY2C-DB3)") (class "Default")
      (node (ref "DISPLAY2") (pin "8") (pinfunction "DB3_8") (pintype "bidirectional"))
      (node (ref "IC6") (pin "2") (pinfunction "PE3_2") (pintype "bidirectional"))
    )
    (net (code "23") (name "Net-(DISPLAY2C-DB4)") (class "Default")
      (node (ref "DISPLAY2") (pin "10") (pinfunction "DB4_10") (pintype "bidirectional"))
      (node (ref "IC6") (pin "3") (pinfunction "PE4_3") (pintype "bidirectional"))
    )
    (net (code "24") (name "Net-(DISPLAY2C-DB5)") (class "Default")
      (node (ref "DISPLAY2") (pin "12") (pinfunction "DB5_12") (pintype "bidirectional"))
      (node (ref "IC6") (pin "4") (pinfunction "PE5_4") (pintype "bidirectional"))
    )
    (net (code "25") (name "Net-(DISPLAY2C-DB6)") (class "Default")
      (node (ref "DISPLAY2") (pin "14") (pinfunction "DB6_14") (pintype "bidirectional"))
      (node (ref "IC6") (pin "5") (pinfunction "PE6_5") (pintype "bidirectional"))
    )
    (net (code "26") (name "Net-(DISPLAY2C-DB7)") (class "Default")
      (node (ref "DISPLAY2") (pin "16") (pinfunction "DB7_16") (pintype "bidirectional"))
      (node (ref "IC6") (pin "38") (pinfunction "PE7_38") (pintype "bidirectional"))
    )
    (net (code "27") (name "Net-(DISPLAY2C-DB8)") (class "Default")
      (node (ref "DISPLAY2") (pin "13") (pinfunction "DB8_13") (pintype "bidirectional"))
      (node (ref "IC6") (pin "39") (pinfunction "PE8_39") (pintype "bidirectional"))
    )
    (net (code "28") (name "Net-(DISPLAY2C-DB9)") (class "Default")
      (node (ref "DISPLAY2") (pin "15") (pinfunction "DB9_15") (pintype "bidirectional"))
      (node (ref "IC6") (pin "40") (pinfunction "PE9_40") (pintype "bidirectional"))
    )
    (net (code "29") (name "Net-(DISPLAY2C-DB10)") (class "Default")
      (node (ref "DISPLAY2") (pin "17") (pinfunction "DB10_17") (pintype "bidirectional"))
      (node (ref "IC6") (pin "41") (pinfunction "PE10_41") (pintype "bidirectional"))
    )
    (net (code "30") (name "Net-(DISPLAY2C-DB11)") (class "Default")
      (node (ref "DISPLAY2") (pin "19") (pinfunction "DB11_19") (pintype "bidirectional"))
      (node (ref "IC6") (pin "42") (pinfunction "PE11_42") (pintype "bidirectional"))
    )
    (net (code "31") (name "Net-(DISPLAY2C-DB12)") (class "Default")
      (node (ref "DISPLAY2") (pin "21") (pinfunction "DB12_21") (pintype "bidirectional"))
      (node (ref "IC6") (pin "43") (pinfunction "PE12_43") (pintype "bidirectional"))
    )
    (net (code "32") (name "Net-(DISPLAY2C-DB13)") (class "Default")
      (node (ref "DISPLAY2") (pin "23") (pinfunction "DB13_23") (pintype "bidirectional"))
      (node (ref "IC6") (pin "44") (pinfunction "PE13_44") (pintype "bidirectional"))
    )
    (net (code "33") (name "Net-(DISPLAY2C-DB14)") (class "Default")
      (node (ref "DISPLAY2") (pin "25") (pinfunction "DB14_25") (pintype "bidirectional"))
      (node (ref "IC6") (pin "45") (pinfunction "PE14_45") (pintype "bidirectional"))
    )
    (net (code "34") (name "Net-(DISPLAY2C-DB15)") (class "Default")
      (node (ref "DISPLAY2") (pin "27") (pinfunction "DB15_27") (pintype "bidirectional"))
      (node (ref "IC6") (pin "46") (pinfunction "PE15_46") (pintype "bidirectional"))
    )
    (net (code "35") (name "Net-(DISPLAY2D-LED_A+)") (class "Default")
      (node (ref "DISPLAY2") (pin "37") (pinfunction "LED_A+_37") (pintype "bidirectional"))
      (node (ref "R30") (pin "1") (pinfunction "1_1") (pintype "passive"))
    )
    (net (code "36") (name "Net-(I+-P)") (class "Default")
      (node (ref "I+") (pin "1") (pinfunction "P_1") (pintype "passive"))
      (node (ref "K1") (pin "3") (pinfunction "P_3") (pintype "passive"))
      (node (ref "R16") (pin "2") (pinfunction "2_2") (pintype "passive"))
    )
    (net (code "37") (name "Net-(I--P)") (class "Default")
      (node (ref "I-") (pin "1") (pinfunction "P_1") (pintype "passive"))
      (node (ref "K1") (pin "6") (pinfunction "P_6") (pintype "passive"))
      (node (ref "R17") (pin "2") (pinfunction "2_2") (pintype "passive"))
    )
    (net (code "38") (name "Net-(IC1A-INN1)") (class "Default")
      (node (ref "IC1") (pin "10") (pinfunction "INN1_10") (pintype "bidirectional"))
      (node (ref "R18") (pin "S2") (pinfunction "S2_S2") (pintype "passive"))
    )
    (net (code "39") (name "Net-(IC1A-INN2)") (class "Default")
      (node (ref "IC1") (pin "8") (pinfunction "INN2_8") (pintype "bidirectional"))
      (node (ref "IC5") (pin "8") (pinfunction "DA_8") (pintype "bidirectional"))
    )
    (net (code "40") (name "Net-(IC1A-INP1)") (class "Default")
      (node (ref "IC1") (pin "9") (pinfunction "INP1_9") (pintype "bidirectional"))
      (node (ref "R18") (pin "S1") (pinfunction "S1_S1") (pintype "passive"))
      (node (ref "R19") (pin "1") (pinfunction "1_1") (pintype "passive"))
    )
    (net (code "41") (name "Net-(IC1A-INP2)") (class "Default")
      (node (ref "IC1") (pin "7") (pinfunction "INP2_7") (pintype "bidirectional"))
      (node (ref "IC5") (pin "9") (pinfunction "DB_9") (pintype "bidirectional"))
    )
    (net (code "42") (name "Net-(IC1A-VOCM)") (class "Default")
      (node (ref "C8") (pin "1") (pinfunction "1_1") (pintype "passive"))
      (node (ref "IC1") (pin "3") (pinfunction "VOCM_3") (pintype "bidirectional"))
      (node (ref "R5") (pin "1") (pinfunction "1_1") (pintype "passive"))
      (node (ref "R6") (pin "2") (pinfunction "2_2") (pintype "passive"))
    )
    (net (code "43") (name "Net-(IC1A-VON)") (class "Default")
      (node (ref "IC1") (pin "1") (pinfunction "VON_1") (pintype "bidirectional"))
      (node (ref "R2") (pin "1") (pinfunction "1_1") (pintype "passive"))
    )
    (net (code "44") (name "Net-(IC1A-VOP)") (class "Default")
      (node (ref "IC1") (pin "2") (pinfunction "VOP_2") (pintype "bidirectional"))
      (node (ref "R1") (pin "1") (pinfunction "1_1") (pintype "passive"))
    )
    (net (code "45") (name "Net-(IC1A-VSOP)") (class "Default")
      (node (ref "C5") (pin "1") (pinfunction "1_1") (pintype "passive"))
      (node (ref "IC1") (pin "4") (pinfunction "VSOP_4") (pintype "bidirectional"))
      (node (ref "IC2") (pin "20") (pinfunction "AVDD_20") (pintype "bidirectional"))
      (node (ref "L5") (pin "2") (pinfunction "2_2") (pintype "passive"))
      (node (ref "R5") (pin "2") (pinfunction "2_2") (pintype "passive"))
    )
    (net (code "46") (name "Net-(IC1B-GPIO4)") (class "Default")
      (node (ref "IC1") (pin "20") (pinfunction "GPIO4_20") (pintype "bidirectional"))
      (node (ref "IC2") (pin "6") (pinfunction "/CS_6") (pintype "bidirectional"))
    )
    (net (code "47") (name "Net-(IC1B-GPIO6)") (class "Default")
      (node (ref "IC1") (pin "18") (pinfunction "GPIO6_18") (pintype "bidirectional"))
      (node (ref "R3") (pin "2") (pinfunction "2_2") (pintype "passive"))
      (node (ref "R4") (pin "2") (pinfunction "2_2") (pintype "passive"))
    )
    (net (code "48") (name "Net-(IC1C-SCLK)") (class "Default")
      (node (ref "IC1") (pin "16") (pinfunction "SCLK_16") (pintype "bidirectional"))
      (node (ref "IC2") (pin "7") (pinfunction "SCLK_7") (pintype "bidirectional"))
    )
    (net (code "49") (name "Net-(IC1C-SDI)") (class "Default")
      (node (ref "IC1") (pin "15") (pinfunction "SDI_15") (pintype "bidirectional"))
      (node (ref "IC2") (pin "8") (pinfunction "DIN_8") (pintype "bidirectional"))
    )
    (net (code "50") (name "Net-(IC1C-SDO)") (class "Default")
      (node (ref "IC1") (pin "14") (pinfunction "SDO_14") (pintype "bidirectional"))
      (node (ref "IC2") (pin "9") (pinfunction "DOUT_9") (pintype "bidirectional"))
    )
    (net (code "51") (name "Net-(IC2A-AINN)") (class "Default")
      (node (ref "C1") (pin "1") (pinfunction "1_1") (pintype "passive"))
      (node (ref "IC2") (pin "2") (pinfunction "AINN_2") (pintype "bidirectional"))
      (node (ref "R2") (pin "2") (pinfunction "2_2") (pintype "passive"))
    )
    (net (code "52") (name "Net-(IC2A-AINP)") (class "Default")
      (node (ref "C1") (pin "2") (pinfunction "2_2") (pintype "passive"))
      (node (ref "IC2") (pin "1") (pinfunction "AINP_1") (pintype "bidirectional"))
      (node (ref "R1") (pin "2") (pinfunction "2_2") (pintype "passive"))
    )
    (net (code "53") (name "Net-(IC2A-BYPASS)") (class "Default")
      (node (ref "C3") (pin "1") (pinfunction "1_1") (pintype "passive"))
      (node (ref "IC2") (pin "13") (pinfunction "BYPASS_13") (pintype "bidirectional"))
    )
    (net (code "54") (name "Net-(IC2A-REFOUT)") (class "Default")
      (node (ref "C2") (pin "1") (pinfunction "1_1") (pintype "passive"))
      (node (ref "IC2") (pin "16") (pinfunction "REFOUT_16") (pintype "bidirectional"))
    )
    (net (code "55") (name "Net-(IC2A-VREFN)") (class "Default")
      (node (ref "C4") (pin "2") (pinfunction "2_2") (pintype "passive"))
      (node (ref "IC2") (pin "18") (pinfunction "VREFN_18") (pintype "bidirectional"))
    )
    (net (code "56") (name "Net-(IC2A-VREFP)") (class "Default")
      (node (ref "C4") (pin "1") (pinfunction "1_1") (pintype "passive"))
      (node (ref "IC2") (pin "17") (pinfunction "VREFP_17") (pintype "bidirectional"))
    )
    (net (code "57") (name "Net-(IC2B-SYNCOUT)") (class "Default")
      (node (ref "IC2") (pin "5") (pinfunction "SYNCOUT_5") (pintype "bidirectional"))
      (node (ref "R3") (pin "1") (pinfunction "1_1") (pintype "passive"))
    )
    (net (code "58") (name "Net-(IC3A-+IN)") (class "Default")
      (node (ref "C10") (pin "1") (pinfunction "1_1") (pintype "passive"))
      (node (ref "IC3") (pin "10") (pinfunction "+IN_10") (pintype "input"))
      (node (ref "IC3") (pin "3") (pinfunction "+IN_3") (pintype "input"))
      (node (ref "R8") (pin "2") (pinfunction "2_2") (pintype "passive"))
    )
    (net (code "59") (name "Net-(IC3A--IN)") (class "Default")
      (node (ref "C9") (pin "1") (pinfunction "1_1") (pintype "passive"))
      (node (ref "IC3") (pin "1") (pinfunction "OUT_1") (pintype "output"))
      (node (ref "IC3") (pin "2") (pinfunction "-IN_2") (pintype "input"))
    )
    (net (code "60") (name "Net-(IC3B--IN)") (class "Default")
      (node (ref "IC3") (pin "6") (pinfunction "-IN_6") (pintype "input"))
      (node (ref "IC3") (pin "7") (pinfunction "OUT_7") (pintype "output"))
      (node (ref "R33") (pin "2") (pinfunction "2_2") (pintype "passive"))
      (node (ref "R7") (pin "1") (pinfunction "1_1") (pintype "passive"))
    )
    (net (code "61") (name "Net-(IC3C--IN)") (class "Default")
      (node (ref "C11") (pin "1") (pinfunction "1_1") (pintype "passive"))
      (node (ref "IC3") (pin "8") (pinfunction "OUT_8") (pintype "output"))
      (node (ref "IC3") (pin "9") (pinfunction "-IN_9") (pintype "input"))
    )
    (net (code "62") (name "Net-(IC3D--IN)") (class "Default")
      (node (ref "C38") (pin "2") (pinfunction "2_2") (pintype "passive"))
      (node (ref "IC3") (pin "13") (pinfunction "-IN_13") (pintype "input"))
      (node (ref "R34") (pin "2") (pinfunction "2_2") (pintype "passive"))
      (node (ref "R35") (pin "2") (pinfunction "2_2") (pintype "passive"))
    )
    (net (code "63") (name "Net-(IC3D-OUT)") (class "Default")
      (node (ref "C38") (pin "1") (pinfunction "1_1") (pintype "passive"))
      (node (ref "IC3") (pin "14") (pinfunction "OUT_14") (pintype "output"))
      (node (ref "IC7") (pin "3") (pinfunction "+IN_3") (pintype "input"))
      (node (ref "R35") (pin "1") (pinfunction "1_1") (pintype "passive"))
    )
    (net (code "64") (name "Net-(IC4-DA)") (class "Default")
      (node (ref "C19") (pin "1") (pinfunction "1_1") (pintype "passive"))
      (node (ref "IC4") (pin "8") (pinfunction "DA_8") (pintype "bidirectional"))
      (node (ref "IC5") (pin "6") (pinfunction "S3A_6") (pintype "bidirectional"))
    )
    (net (code "65") (name "Net-(IC4-DB)") (class "Default")
      (node (ref "IC4") (pin "9") (pinfunction "DB_9") (pintype "bidirectional"))
      (node (ref "IC7") (pin "7") (pinfunction "OUT_7") (pintype "output"))
    )
    (net (code "66") (name "Net-(IC4-S1A)") (class "Default")
      (node (ref "IC4") (pin "13") (pinfunction "S1B_13") (pintype "bidirectional"))
      (node (ref "IC4") (pin "4") (pinfunction "S1A_4") (pintype "bidirectional"))
      (node (ref "R27") (pin "1") (pinfunction "1_1") (pintype "passive"))
    )
    (net (code "67") (name "Net-(IC4-S2A)") (class "Default")
      (node (ref "IC4") (pin "12") (pinfunction "S2B_12") (pintype "bidirectional"))
      (node (ref "IC4") (pin "5") (pinfunction "S2A_5") (pintype "bidirectional"))
      (node (ref "R26") (pin "1") (pinfunction "1_1") (pintype "passive"))
    )
    (net (code "68") (name "Net-(IC4-S3A)") (class "Default")
      (node (ref "IC4") (pin "11") (pinfunction "S3B_11") (pintype "bidirectional"))
      (node (ref "IC4") (pin "6") (pinfunction "S3A_6") (pintype "bidirectional"))
      (node (ref "R25") (pin "1") (pinfunction "1_1") (pintype "passive"))
    )
    (net (code "69") (name "Net-(IC4-S4A)") (class "Default")
      (node (ref "IC4") (pin "10") (pinfunction "S4B_10") (pintype "bidirectional"))
      (node (ref "IC4") (pin "7") (pinfunction "S4A_7") (pintype "bidirectional"))
      (node (ref "R24") (pin "1") (pinfunction "1_1") (pintype "passive"))
    )
    (net (code "70") (name "Net-(IC5-S1A)") (class "Default")
      (node (ref "C16") (pin "2") (pinfunction "2_2") (pintype "passive"))
      (node (ref "IC5") (pin "4") (pinfunction "S1A_4") (pintype "bidirectional"))
      (node (ref "R12") (pin "1") (pinfunction "1_1") (pintype "passive"))
    )
    (net (code "71") (name "Net-(IC5-S1B)") (class "Default")
      (node (ref "C18") (pin "1") (pinfunction "1_1") (pintype "passive"))
      (node (ref "IC5") (pin "13") (pinfunction "S1B_13") (pintype "bidirectional"))
      (node (ref "R13") (pin "1") (pinfunction "1_1") (pintype "passive"))
    )
    (net (code "72") (name "Net-(IC5-S2A)") (class "Default")
      (node (ref "C16") (pin "1") (pinfunction "1_1") (pintype "passive"))
      (node (ref "IC5") (pin "5") (pinfunction "S2A_5") (pintype "bidirectional"))
      (node (ref "R16") (pin "1") (pinfunction "1_1") (pintype "passive"))
      (node (ref "U+") (pin "1") (pinfunction "P_1") (pintype "passive"))
    )
    (net (code "73") (name "Net-(IC5-S2B)") (class "Default")
      (node (ref "C18") (pin "2") (pinfunction "2_2") (pintype "passive"))
      (node (ref "IC5") (pin "12") (pinfunction "S2B_12") (pintype "bidirectional"))
      (node (ref "R17") (pin "1") (pinfunction "1_1") (pintype "passive"))
      (node (ref "U-") (pin "1") (pinfunction "P_1") (pintype "passive"))
    )
    (net (code "74") (name "Net-(IC5-S3B)") (class "Default")
      (node (ref "C17") (pin "2") (pinfunction "2_2") (pintype "passive"))
      (node (ref "IC5") (pin "11") (pinfunction "S3B_11") (pintype "bidirectional"))
      (node (ref "K1") (pin "7") (pinfunction "O_7") (pintype "passive"))
      (node (ref "R24") (pin "2") (pinfunction "2_2") (pintype "passive"))
      (node (ref "R25") (pin "2") (pinfunction "2_2") (pintype "passive"))
      (node (ref "R26") (pin "2") (pinfunction "2_2") (pintype "passive"))
      (node (ref "R27") (pin "2") (pinfunction "2_2") (pintype "passive"))
      (node (ref "R28") (pin "2") (pinfunction "2_2") (pintype "passive"))
    )
    (net (code "75") (name "Net-(IC5-S4A)") (class "Default")
      (node (ref "C19") (pin "2") (pinfunction "2_2") (pintype "passive"))
      (node (ref "IC5") (pin "7") (pinfunction "S4A_7") (pintype "bidirectional"))
      (node (ref "R14") (pin "1") (pinfunction "1_1") (pintype "passive"))
    )
    (net (code "76") (name "Net-(IC5-S4B)") (class "Default")
      (node (ref "C17") (pin "1") (pinfunction "1_1") (pintype "passive"))
      (node (ref "IC5") (pin "10") (pinfunction "S4B_10") (pintype "bidirectional"))
      (node (ref "R15") (pin "1") (pinfunction "1_1") (pintype "passive"))
    )
    (net (code "77") (name "Net-(IC6A-NRST)") (class "Default")
      (node (ref "C25") (pin "1") (pinfunction "1_1") (pintype "passive"))
      (node (ref "IC6") (pin "14") (pinfunction "NRST_14") (pintype "bidirectional"))
      (node (ref "R29") (pin "2") (pinfunction "2_2") (pintype "passive"))
    )
    (net (code "78") (name "Net-(IC6A-OSC_IN)") (class "Default")
      (node (ref "C15") (pin "1") (pinfunction "1_1") (pintype "passive"))
      (node (ref "IC6") (pin "12") (pinfunction "OSC_IN_12") (pintype "bidirectional"))
      (node (ref "Y1") (pin "3") (pinfunction "2_3") (pintype "passive"))
    )
    (net (code "79") (name "Net-(IC6A-OSC_OUT)") (class "Default")
      (node (ref "C14") (pin "1") (pinfunction "1_1") (pintype "passive"))
      (node (ref "IC6") (pin "13") (pinfunction "OSC_OUT_13") (pintype "bidirectional"))
      (node (ref "Y1") (pin "1") (pinfunction "1_1") (pintype "passive"))
    )
    (net (code "80") (name "Net-(IC6A-PA9)") (class "Default")
      (node (ref "IC6") (pin "68") (pinfunction "PA9_68") (pintype "bidirectional"))
      (node (ref "UART") (pin "3") (pinfunction "3_3") (pintype "passive"))
    )
    (net (code "81") (name "Net-(IC6A-PA10)") (class "Default")
      (node (ref "IC6") (pin "69") (pinfunction "PA10_69") (pintype "bidirectional"))
      (node (ref "UART") (pin "1") (pinfunction "1_1") (pintype "passive"))
    )
    (net (code "82") (name "Net-(IC6A-VDDA)") (class "Default")
      (node (ref "C20") (pin "1") (pinfunction "1_1") (pintype "passive"))
      (node (ref "IC6") (pin "22") (pinfunction "VDDA_22") (pintype "power_in"))
      (node (ref "L2") (pin "2") (pinfunction "2_2") (pintype "passive"))
    )
    (net (code "83") (name "Net-(IC7A--IN)") (class "Default")
      (node (ref "C12") (pin "2") (pinfunction "2_2") (pintype "passive"))
      (node (ref "IC7") (pin "2") (pinfunction "-IN_2") (pintype "input"))
      (node (ref "R10") (pin "1") (pinfunction "1_1") (pintype "passive"))
      (node (ref "R9") (pin "2") (pinfunction "2_2") (pintype "passive"))
    )
    (net (code "84") (name "Net-(IC7A-OUT)") (class "Default")
      (node (ref "C12") (pin "1") (pinfunction "1_1") (pintype "passive"))
      (node (ref "IC7") (pin "1") (pinfunction "OUT_1") (pintype "output"))
      (node (ref "R10") (pin "2") (pinfunction "2_2") (pintype "passive"))
      (node (ref "R11") (pin "1") (pinfunction "1_1") (pintype "passive"))
    )
    (net (code "85") (name "Net-(IC7B--IN)") (class "Default")
      (node (ref "IC7") (pin "6") (pinfunction "-IN_6") (pintype "input"))
      (node (ref "R28") (pin "1") (pinfunction "1_1") (pintype "passive"))
    )
    (net (code "86") (name "Net-(IC8-SW)") (class "Default")
      (node (ref "C28") (pin "2") (pinfunction "2_2") (pintype "passive"))
      (node (ref "D1") (pin "A") (pinfunction "A_A") (pintype "passive"))
      (node (ref "IC8") (pin "1") (pinfunction "SW_1") (pintype "bidirectional"))
      (node (ref "L1") (pin "2") (pinfunction "2_2") (pintype "passive"))
    )
    (net (code "87") (name "Net-(IC8-VFB)") (class "Default")
      (node (ref "IC8") (pin "3") (pinfunction "VFB_3") (pintype "bidirectional"))
      (node (ref "R23") (pin "2") (pinfunction "2_2") (pintype "passive"))
      (node (ref "R31") (pin "1") (pinfunction "1_1") (pintype "passive"))
    )
    (net (code "88") (name "Net-(IC10-+IN)") (class "Default")
      (node (ref "C37") (pin "1") (pinfunction "1_1") (pintype "passive"))
      (node (ref "IC10") (pin "3") (pinfunction "+IN_3") (pintype "input"))
      (node (ref "R32") (pin "2") (pinfunction "2_2") (pintype "passive"))
      (node (ref "R33") (pin "1") (pinfunction "1_1") (pintype "passive"))
    )
    (net (code "89") (name "Net-(IC10--IN)") (class "Default")
      (node (ref "C13") (pin "2") (pinfunction "2_2") (pintype "passive"))
      (node (ref "IC10") (pin "2") (pinfunction "-IN_2") (pintype "input"))
      (node (ref "R19") (pin "2") (pinfunction "2_2") (pintype "passive"))
    )
    (net (code "90") (name "Net-(IC10-OUT)") (class "Default")
      (node (ref "C13") (pin "1") (pinfunction "1_1") (pintype "passive"))
      (node (ref "IC10") (pin "6") (pinfunction "OUT_6") (pintype "output"))
      (node (ref "R20") (pin "2") (pinfunction "2_2") (pintype "passive"))
    )
    (net (code "91") (name "Net-(IC12-IN)") (class "Default")
      (node (ref "C30") (pin "1") (pinfunction "1_1") (pintype "passive"))
      (node (ref "IC12") (pin "8") (pinfunction "IN_8") (pintype "input"))
      (node (ref "L4") (pin "2") (pinfunction "2_2") (pintype "passive"))
    )
    (net (code "92") (name "Net-(K1A-O)") (class "Default")
      (node (ref "K1") (pin "2") (pinfunction "O_2") (pintype "passive"))
      (node (ref "R11") (pin "2") (pinfunction "2_2") (pintype "passive"))
    )
    (net (code "93") (name "Net-(K1B-S)") (class "Default")
      (node (ref "K1") (pin "5") (pinfunction "S_5") (pintype "passive"))
      (node (ref "T1") (pin "3") (pinfunction "D_3") (pintype "passive"))
    )
    (net (code "94") (name "Net-(R21-Pad2)") (class "Default")
      (node (ref "R21") (pin "2") (pinfunction "2_2") (pintype "passive"))
      (node (ref "X1") (pin "2") (pinfunction "2_2") (pintype "passive"))
    )
    (net (code "95") (name "Net-(R22-Pad2)") (class "Default")
      (node (ref "R22") (pin "2") (pinfunction "2_2") (pintype "passive"))
      (node (ref "X1") (pin "3") (pinfunction "3_3") (pintype "passive"))
    )
    (net (code "96") (name "Net-(T1-G)") (class "Default")
      (node (ref "R20") (pin "1") (pinfunction "1_1") (pintype "passive"))
      (node (ref "T1") (pin "1") (pinfunction "G_1") (pintype "passive"))
    )
    (net (code "97") (name "Net-(T1-S)") (class "Default")
      (node (ref "R18") (pin "I1") (pinfunction "I1_I1") (pintype "passive"))
      (node (ref "T1") (pin "2") (pinfunction "S_2") (pintype "passive"))
    )
    (net (code "98") (name "PGAMUX0") (class "Default")
      (node (ref "IC1") (pin "24") (pinfunction "GPIO0_24") (pintype "bidirectional"))
      (node (ref "IC5") (pin "1") (pinfunction "A0_1") (pintype "bidirectional"))
    )
    (net (code "99") (name "PGAMUX1") (class "Default")
      (node (ref "IC1") (pin "23") (pinfunction "GPIO1_23") (pintype "bidirectional"))
      (node (ref "IC5") (pin "16") (pinfunction "A1_16") (pintype "bidirectional"))
    )
    (net (code "100") (name "SWCLK") (class "Default")
      (node (ref "IC6") (pin "76") (pinfunction "PA14_76") (pintype "bidirectional"))
      (node (ref "UART1") (pin "1") (pinfunction "1_1") (pintype "passive"))
    )
    (net (code "101") (name "SWDIO") (class "Default")
      (node (ref "IC6") (pin "72") (pinfunction "PA13_72") (pintype "bidirectional"))
      (node (ref "UART1") (pin "3") (pinfunction "3_3") (pintype "passive"))
    )
    (net (code "102") (name "TFT_CS") (class "Default")
      (node (ref "DISPLAY2") (pin "29") (pinfunction "CS_29") (pintype "bidirectional"))
      (node (ref "IC6") (pin "48") (pinfunction "PB11_48") (pintype "bidirectional"))
    )
    (net (code "103") (name "TFT_RD") (class "Default")
      (node (ref "DISPLAY2") (pin "11") (pinfunction "RD_11") (pintype "bidirectional"))
      (node (ref "IC6") (pin "37") (pinfunction "PB2_37") (pintype "bidirectional"))
    )
    (net (code "104") (name "TFT_RS") (class "Default")
      (node (ref "DISPLAY2") (pin "7") (pinfunction "RS_7") (pintype "bidirectional"))
      (node (ref "IC6") (pin "7") (pinfunction "PC13_7") (pintype "bidirectional"))
    )
    (net (code "105") (name "TFT_RST") (class "Default")
      (node (ref "DISPLAY2") (pin "33") (pinfunction "RST_33") (pintype "bidirectional"))
      (node (ref "IC6") (pin "55") (pinfunction "PD8_55") (pintype "bidirectional"))
    )
    (net (code "106") (name "TFT_WR") (class "Default")
      (node (ref "DISPLAY2") (pin "9") (pinfunction "WR_9") (pintype "bidirectional"))
      (node (ref "IC6") (pin "8") (pinfunction "PC14_8") (pintype "bidirectional"))
    )
    (net (code "107") (name "USB_N") (class "Default")
      (node (ref "IC6") (pin "70") (pinfunction "PA11_70") (pintype "bidirectional"))
      (node (ref "R21") (pin "1") (pinfunction "1_1") (pintype "passive"))
    )
    (net (code "108") (name "USB_P") (class "Default")
      (node (ref "IC6") (pin "71") (pinfunction "PA12_71") (pintype "bidirectional"))
      (node (ref "R22") (pin "1") (pinfunction "1_1") (pintype "passive"))
    )
    (net (code "109") (name "unconnected-(DISPLAY2A-BUSY-Pad24)") (class "Default")
      (node (ref "DISPLAY2") (pin "24") (pinfunction "BUSY_24") (pintype "bidirectional"))
    )
    (net (code "110") (name "unconnected-(IC1B-GPIO2-Pad22)") (class "Default")
      (node (ref "IC1") (pin "22") (pinfunction "GPIO2_22") (pintype "bidirectional"))
    )
    (net (code "111") (name "unconnected-(IC1B-GPIO3-Pad21)") (class "Default")
      (node (ref "IC1") (pin "21") (pinfunction "GPIO3_21") (pintype "bidirectional"))
    )
    (net (code "112") (name "unconnected-(IC1B-GPIO5-Pad19)") (class "Default")
      (node (ref "IC1") (pin "19") (pinfunction "GPIO5_19") (pintype "bidirectional"))
    )
    (net (code "113") (name "unconnected-(IC1C-{slash}CS-Pad17)") (class "Default")
      (node (ref "IC1") (pin "17") (pinfunction "/CS_17") (pintype "bidirectional"))
    )
    (net (code "114") (name "unconnected-(IC2B-RST-Pad3)") (class "Default")
      (node (ref "IC2") (pin "3") (pinfunction "RST_3") (pintype "bidirectional"))
    )
    (net (code "115") (name "unconnected-(IC2B-START-Pad4)") (class "Default")
      (node (ref "IC2") (pin "4") (pinfunction "START_4") (pintype "bidirectional"))
    )
    (net (code "116") (name "unconnected-(IC2B-XTAL2-Pad12)") (class "Default")
      (node (ref "IC2") (pin "12") (pinfunction "XTAL2_12") (pintype "bidirectional"))
    )
    (net (code "117") (name "unconnected-(IC2B-{slash}DRDY-Pad10)") (class "Default")
      (node (ref "IC2") (pin "10") (pinfunction "/DRDY_10") (pintype "bidirectional"))
    )
    (net (code "118") (name "unconnected-(IC3B-+IN-Pad5)") (class "Default")
      (node (ref "IC3") (pin "5") (pinfunction "+IN_5") (pintype "input"))
    )
    (net (code "119") (name "unconnected-(IC3D-+IN-Pad12)") (class "Default")
      (node (ref "IC3") (pin "12") (pinfunction "+IN_12") (pintype "input"))
    )
    (net (code "120") (name "unconnected-(IC4-A0-Pad1)") (class "Default")
      (node (ref "IC4") (pin "1") (pinfunction "A0_1") (pintype "bidirectional"))
    )
    (net (code "121") (name "unconnected-(IC4-A1-Pad16)") (class "Default")
      (node (ref "IC4") (pin "16") (pinfunction "A1_16") (pintype "bidirectional"))
    )
    (net (code "122") (name "unconnected-(IC6A-PA0-WKUP-Pad23)") (class "Default")
      (node (ref "IC6") (pin "23") (pinfunction "PA0-WKUP_23") (pintype "bidirectional"))
    )
    (net (code "123") (name "unconnected-(IC6A-PA1-Pad24)") (class "Default")
      (node (ref "IC6") (pin "24") (pinfunction "PA1_24") (pintype "bidirectional"))
    )
    (net (code "124") (name "unconnected-(IC6A-PA2-Pad25)") (class "Default")
      (node (ref "IC6") (pin "25") (pinfunction "PA2_25") (pintype "bidirectional"))
    )
    (net (code "125") (name "unconnected-(IC6A-PA3-Pad26)") (class "Default")
      (node (ref "IC6") (pin "26") (pinfunction "PA3_26") (pintype "bidirectional"))
    )
    (net (code "126") (name "unconnected-(IC6A-PA4-Pad29)") (class "Default")
      (node (ref "IC6") (pin "29") (pinfunction "PA4_29") (pintype "bidirectional"))
    )
    (net (code "127") (name "unconnected-(IC6A-PA5-Pad30)") (class "Default")
      (node (ref "IC6") (pin "30") (pinfunction "PA5_30") (pintype "bidirectional"))
    )
    (net (code "128") (name "unconnected-(IC6A-PA6-Pad31)") (class "Default")
      (node (ref "IC6") (pin "31") (pinfunction "PA6_31") (pintype "bidirectional"))
    )
    (net (code "129") (name "unconnected-(IC6A-PA7-Pad32)") (class "Default")
      (node (ref "IC6") (pin "32") (pinfunction "PA7_32") (pintype "bidirectional"))
    )
    (net (code "130") (name "unconnected-(IC6A-PA8-Pad67)") (class "Default")
      (node (ref "IC6") (pin "67") (pinfunction "PA8_67") (pintype "bidirectional"))
    )
    (net (code "131") (name "unconnected-(IC6A-PA15-Pad77)") (class "Default")
      (node (ref "IC6") (pin "77") (pinfunction "PA15_77") (pintype "bidirectional"))
    )
    (net (code "132") (name "unconnected-(IC6A-PB0-Pad35)") (class "Default")
      (node (ref "IC6") (pin "35") (pinfunction "PB0_35") (pintype "bidirectional"))
    )
    (net (code "133") (name "unconnected-(IC6A-PB3-Pad89)") (class "Default")
      (node (ref "IC6") (pin "89") (pinfunction "PB3_89") (pintype "bidirectional"))
    )
    (net (code "134") (name "unconnected-(IC6A-PB4-Pad90)") (class "Default")
      (node (ref "IC6") (pin "90") (pinfunction "PB4_90") (pintype "bidirectional"))
    )
    (net (code "135") (name "unconnected-(IC6A-PB5-Pad91)") (class "Default")
      (node (ref "IC6") (pin "91") (pinfunction "PB5_91") (pintype "bidirectional"))
    )
    (net (code "136") (name "unconnected-(IC6A-PB6-Pad92)") (class "Default")
      (node (ref "IC6") (pin "92") (pinfunction "PB6_92") (pintype "bidirectional"))
    )
    (net (code "137") (name "unconnected-(IC6A-PB7-Pad93)") (class "Default")
      (node (ref "IC6") (pin "93") (pinfunction "PB7_93") (pintype "bidirectional"))
    )
    (net (code "138") (name "unconnected-(IC6A-PB8-Pad95)") (class "Default")
      (node (ref "IC6") (pin "95") (pinfunction "PB8_95") (pintype "bidirectional"))
    )
    (net (code "139") (name "unconnected-(IC6A-PB9-Pad96)") (class "Default")
      (node (ref "IC6") (pin "96") (pinfunction "PB9_96") (pintype "bidirectional"))
    )
    (net (code "140") (name "unconnected-(IC6A-PC0-Pad15)") (class "Default")
      (node (ref "IC6") (pin "15") (pinfunction "PC0_15") (pintype "bidirectional"))
    )
    (net (code "141") (name "unconnected-(IC6A-PC1-Pad16)") (class "Default")
      (node (ref "IC6") (pin "16") (pinfunction "PC1_16") (pintype "bidirectional"))
    )
    (net (code "142") (name "unconnected-(IC6A-PC2-Pad17)") (class "Default")
      (node (ref "IC6") (pin "17") (pinfunction "PC2_17") (pintype "bidirectional"))
    )
    (net (code "143") (name "unconnected-(IC6A-PC3-Pad18)") (class "Default")
      (node (ref "IC6") (pin "18") (pinfunction "PC3_18") (pintype "bidirectional"))
    )
    (net (code "144") (name "unconnected-(IC6A-PC4-Pad33)") (class "Default")
      (node (ref "IC6") (pin "33") (pinfunction "PC4_33") (pintype "bidirectional"))
    )
    (net (code "145") (name "unconnected-(IC6A-PC5-Pad34)") (class "Default")
      (node (ref "IC6") (pin "34") (pinfunction "PC5_34") (pintype "bidirectional"))
    )
    (net (code "146") (name "unconnected-(IC6A-PC6-Pad63)") (class "Default")
      (node (ref "IC6") (pin "63") (pinfunction "PC6_63") (pintype "bidirectional"))
    )
    (net (code "147") (name "unconnected-(IC6A-PC7-Pad64)") (class "Default")
      (node (ref "IC6") (pin "64") (pinfunction "PC7_64") (pintype "bidirectional"))
    )
    (net (code "148") (name "unconnected-(IC6A-PC8-Pad65)") (class "Default")
      (node (ref "IC6") (pin "65") (pinfunction "PC8_65") (pintype "bidirectional"))
    )
    (net (code "149") (name "unconnected-(IC6A-PC9-Pad66)") (class "Default")
      (node (ref "IC6") (pin "66") (pinfunction "PC9_66") (pintype "bidirectional"))
    )
    (net (code "150") (name "unconnected-(IC6A-PC10-Pad78)") (class "Default")
      (node (ref "IC6") (pin "78") (pinfunction "PC10_78") (pintype "bidirectional"))
    )
    (net (code "151") (name "unconnected-(IC6A-PC11-Pad79)") (class "Default")
      (node (ref "IC6") (pin "79") (pinfunction "PC11_79") (pintype "bidirectional"))
    )
    (net (code "152") (name "unconnected-(IC6A-PC12-Pad80)") (class "Default")
      (node (ref "IC6") (pin "80") (pinfunction "PC12_80") (pintype "bidirectional"))
    )
    (net (code "153") (name "unconnected-(IC6A-PC15-Pad9)") (class "Default")
      (node (ref "IC6") (pin "9") (pinfunction "PC15_9") (pintype "bidirectional"))
    )
    (net (code "154") (name "unconnected-(IC6A-PD0-Pad81)") (class "Default")
      (node (ref "IC6") (pin "81") (pinfunction "PD0_81") (pintype "bidirectional"))
    )
    (net (code "155") (name "unconnected-(IC6A-PD1-Pad82)") (class "Default")
      (node (ref "IC6") (pin "82") (pinfunction "PD1_82") (pintype "bidirectional"))
    )
    (net (code "156") (name "unconnected-(IC6A-PD2-Pad83)") (class "Default")
      (node (ref "IC6") (pin "83") (pinfunction "PD2_83") (pintype "bidirectional"))
    )
    (net (code "157") (name "unconnected-(IC6A-PD3-Pad84)") (class "Default")
      (node (ref "IC6") (pin "84") (pinfunction "PD3_84") (pintype "bidirectional"))
    )
    (net (code "158") (name "unconnected-(IC6A-PD4-Pad85)") (class "Default")
      (node (ref "IC6") (pin "85") (pinfunction "PD4_85") (pintype "bidirectional"))
    )
    (net (code "159") (name "unconnected-(IC6A-PD5-Pad86)") (class "Default")
      (node (ref "IC6") (pin "86") (pinfunction "PD5_86") (pintype "bidirectional"))
    )
    (net (code "160") (name "unconnected-(IC6A-PD6-Pad87)") (class "Default")
      (node (ref "IC6") (pin "87") (pinfunction "PD6_87") (pintype "bidirectional"))
    )
    (net (code "161") (name "unconnected-(IC6A-PD7-Pad88)") (class "Default")
      (node (ref "IC6") (pin "88") (pinfunction "PD7_88") (pintype "bidirectional"))
    )
    (net (code "162") (name "unconnected-(IC6A-PD9-Pad56)") (class "Default")
      (node (ref "IC6") (pin "56") (pinfunction "PD9_56") (pintype "bidirectional"))
    )
    (net (code "163") (name "unconnected-(IC6A-PD10-Pad57)") (class "Default")
      (node (ref "IC6") (pin "57") (pinfunction "PD10_57") (pintype "bidirectional"))
    )
    (net (code "164") (name "unconnected-(IC6A-PD11-Pad58)") (class "Default")
      (node (ref "IC6") (pin "58") (pinfunction "PD11_58") (pintype "bidirectional"))
    )
    (net (code "165") (name "unconnected-(IC6A-PD12-Pad59)") (class "Default")
      (node (ref "IC6") (pin "59") (pinfunction "PD12_59") (pintype "bidirectional"))
    )
    (net (code "166") (name "unconnected-(IC6A-PD13-Pad60)") (class "Default")
      (node (ref "IC6") (pin "60") (pinfunction "PD13_60") (pintype "bidirectional"))
    )
    (net (code "167") (name "unconnected-(IC6A-PD14-Pad61)") (class "Default")
      (node (ref "IC6") (pin "61") (pinfunction "PD14_61") (pintype "bidirectional"))
    )
    (net (code "168") (name "unconnected-(IC6A-PD15-Pad62)") (class "Default")
      (node (ref "IC6") (pin "62") (pinfunction "PD15_62") (pintype "bidirectional"))
    )
    (net (code "169") (name "unconnected-(IC6A-PF2-Pad19)") (class "Default")
      (node (ref "IC6") (pin "19") (pinfunction "PF2_19") (pintype "bidirectional"))
    )
    (net (code "170") (name "unconnected-(IC6A-PF4-Pad27)") (class "Default")
      (node (ref "IC6") (pin "27") (pinfunction "PF4_27") (pintype "bidirectional"))
    )
    (net (code "171") (name "unconnected-(IC6A-PF6-Pad73)") (class "Default")
      (node (ref "IC6") (pin "73") (pinfunction "PF6_73") (pintype "bidirectional"))
    )
    (net (code "172") (name "unconnected-(IC6A-PF9-Pad10)") (class "Default")
      (node (ref "IC6") (pin "10") (pinfunction "PF9_10") (pintype "bidirectional"))
    )
    (net (code "173") (name "unconnected-(IC6A-PF10-Pad11)") (class "Default")
      (node (ref "IC6") (pin "11") (pinfunction "PF10_11") (pintype "bidirectional"))
    )
    (net (code "174") (name "unconnected-(IC10-ON1-Pad1)") (class "Default")
      (node (ref "IC10") (pin "1") (pinfunction "ON1_1") (pintype "passive"))
    )
    (net (code "175") (name "unconnected-(IC10-ON2-Pad8)") (class "Default")
      (node (ref "IC10") (pin "8") (pinfunction "ON2_8") (pintype "passive"))
    )
    (net (code "176") (name "unconnected-(IC10-OPT-Pad5)") (class "Default")
      (node (ref "IC10") (pin "5") (pinfunction "OPT_5") (pintype "passive"))
    )
    (net (code "177") (name "unconnected-(K1C-+-Pad1)") (class "Default")
      (node (ref "K1") (pin "1") (pinfunction "+_1") (pintype "passive"))
    )
    (net (code "178") (name "unconnected-(K1C---Pad8)") (class "Default")
      (node (ref "K1") (pin "8") (pinfunction "-_8") (pintype "passive"))
    )
    (net (code "179") (name "unconnected-(X1-Pad1)") (class "Default")
      (node (ref "X1") (pin "1") (pinfunction "1_1") (pintype "passive"))
    )
  )
)
